# ADAS_ECU_revA.net
KiCad netlist of a schematic drawn in Altium Designer
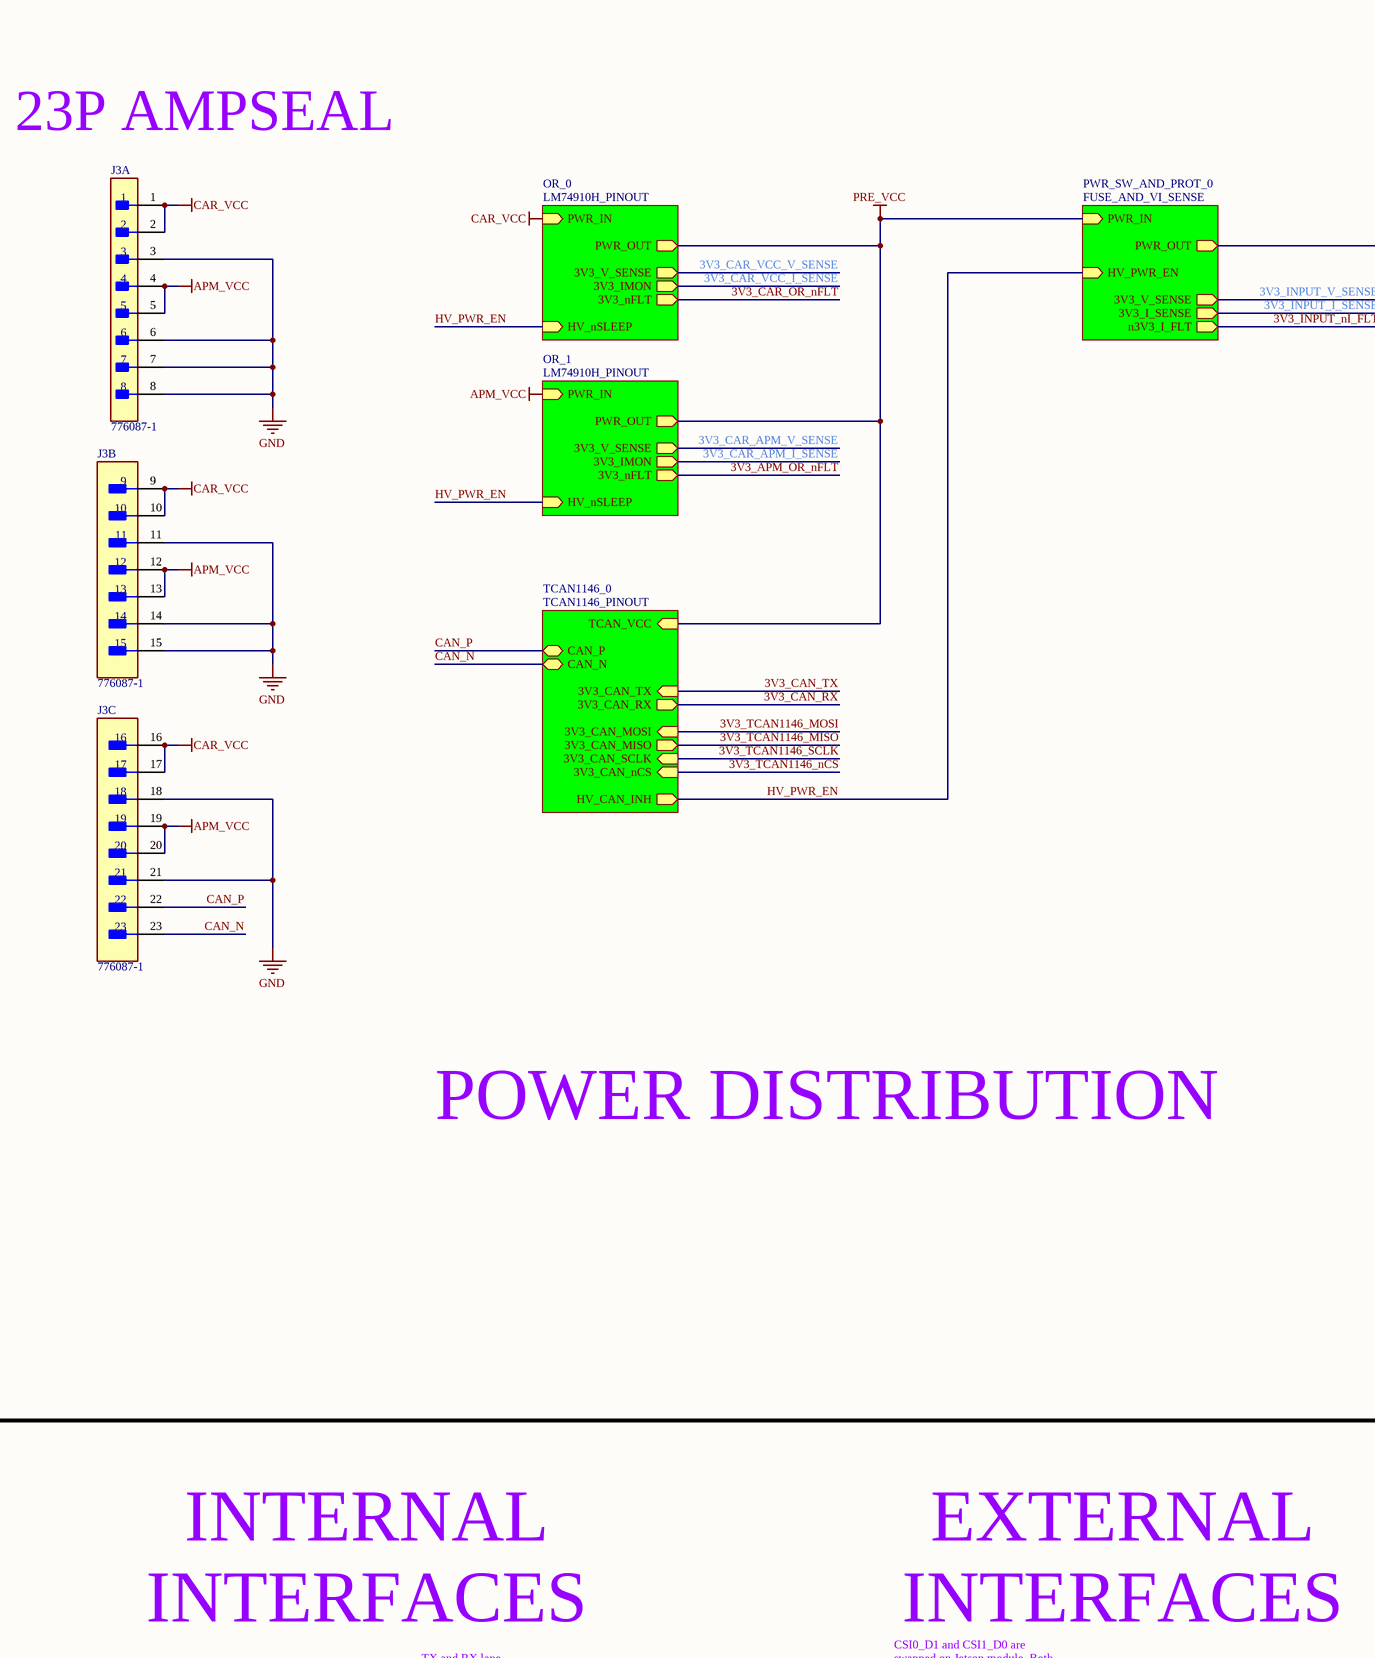
[diagram p0: ADAS_ECU_revA.SchDoc, top column 1 of 4]
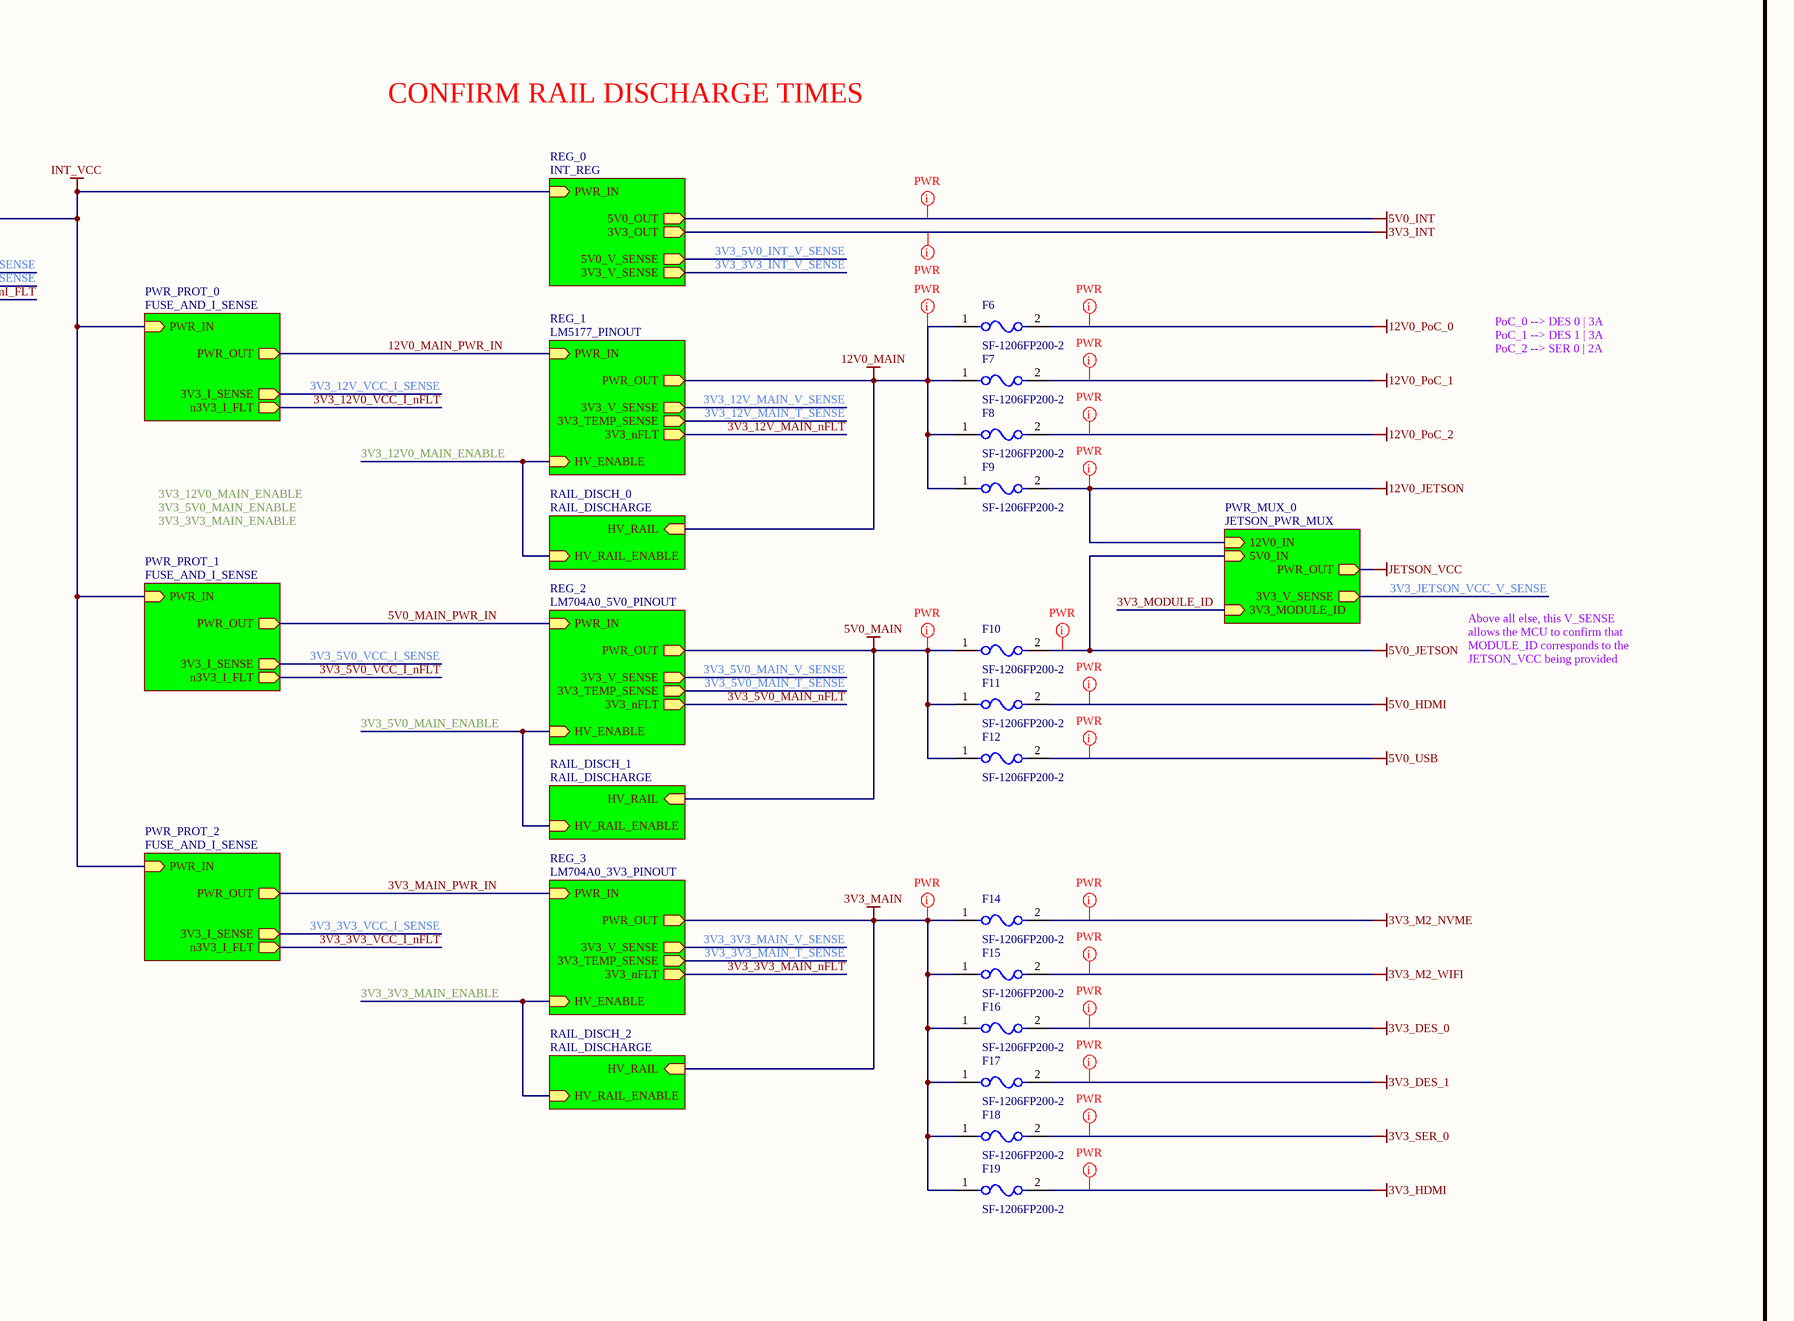
[diagram p1: ADAS_ECU_revA.SchDoc, top column 2 of 4]
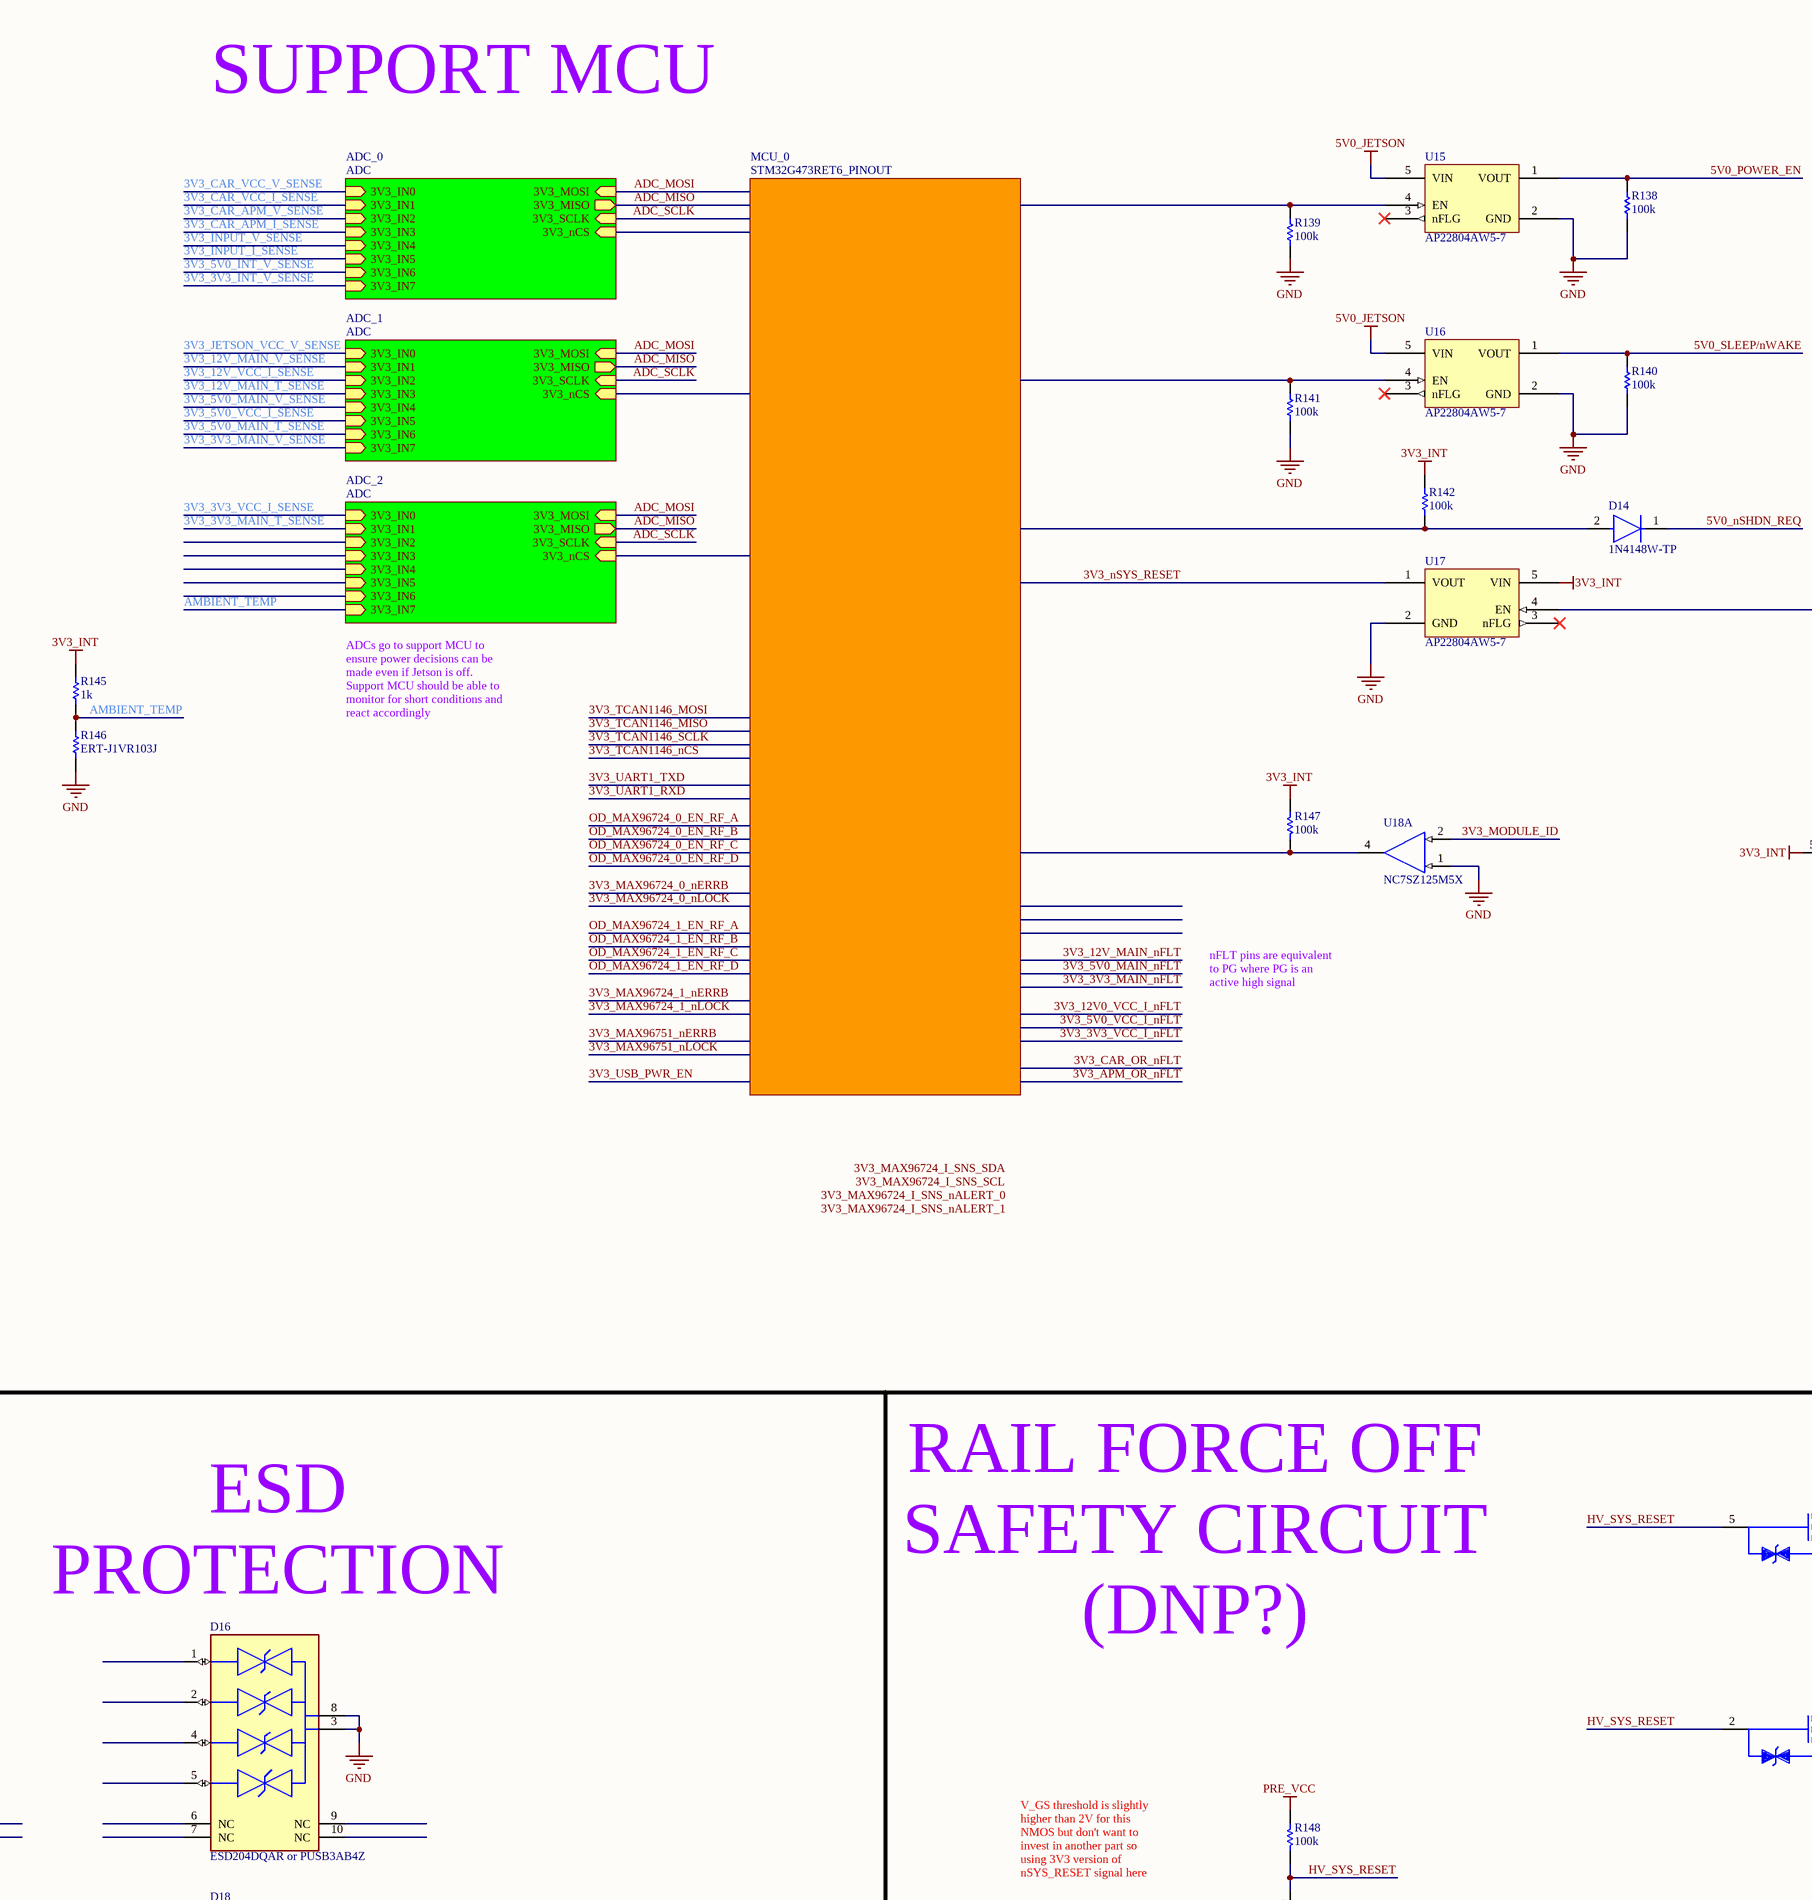
[diagram p2: ADAS_ECU_revA.SchDoc, top column 3 of 4]
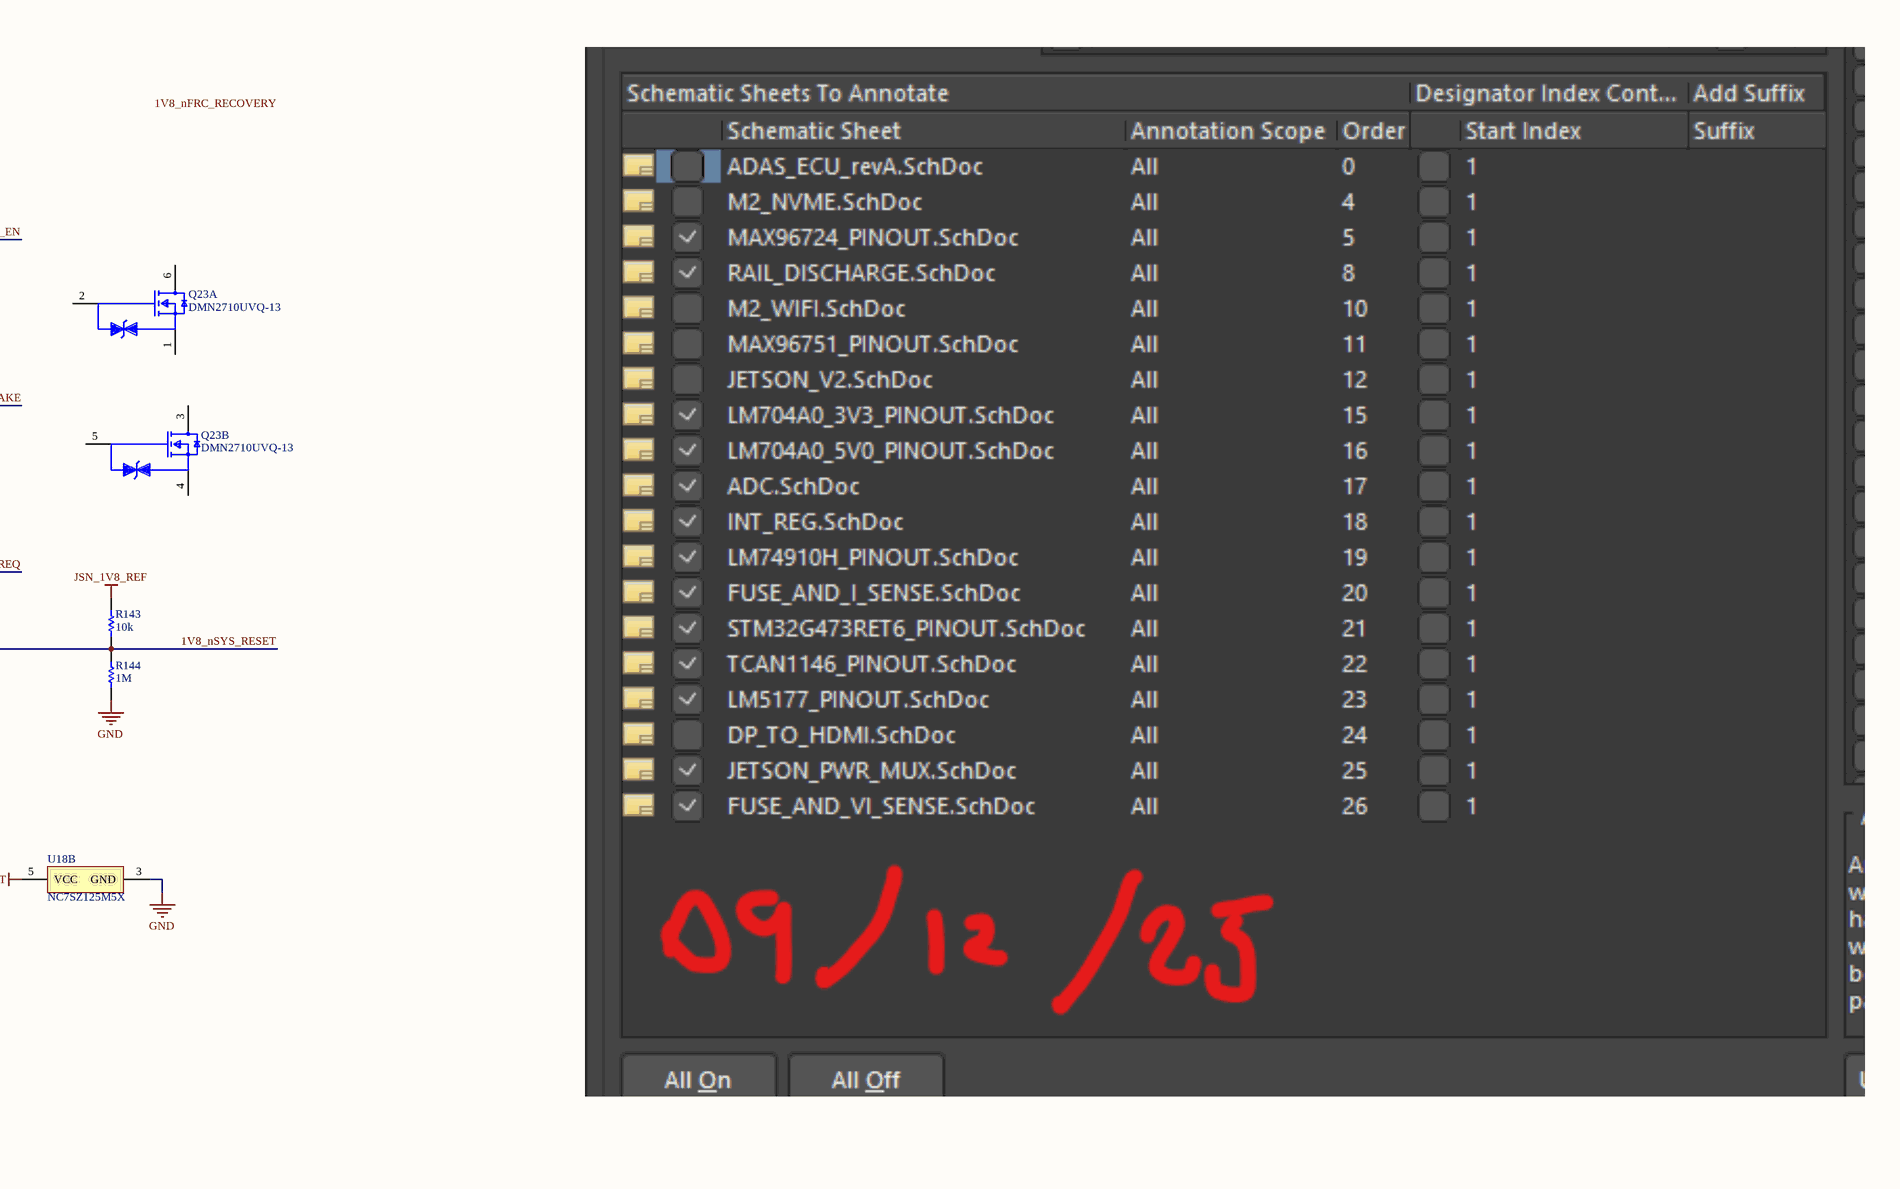
[diagram p3: ADAS_ECU_revA.SchDoc, top column 4 of 4]
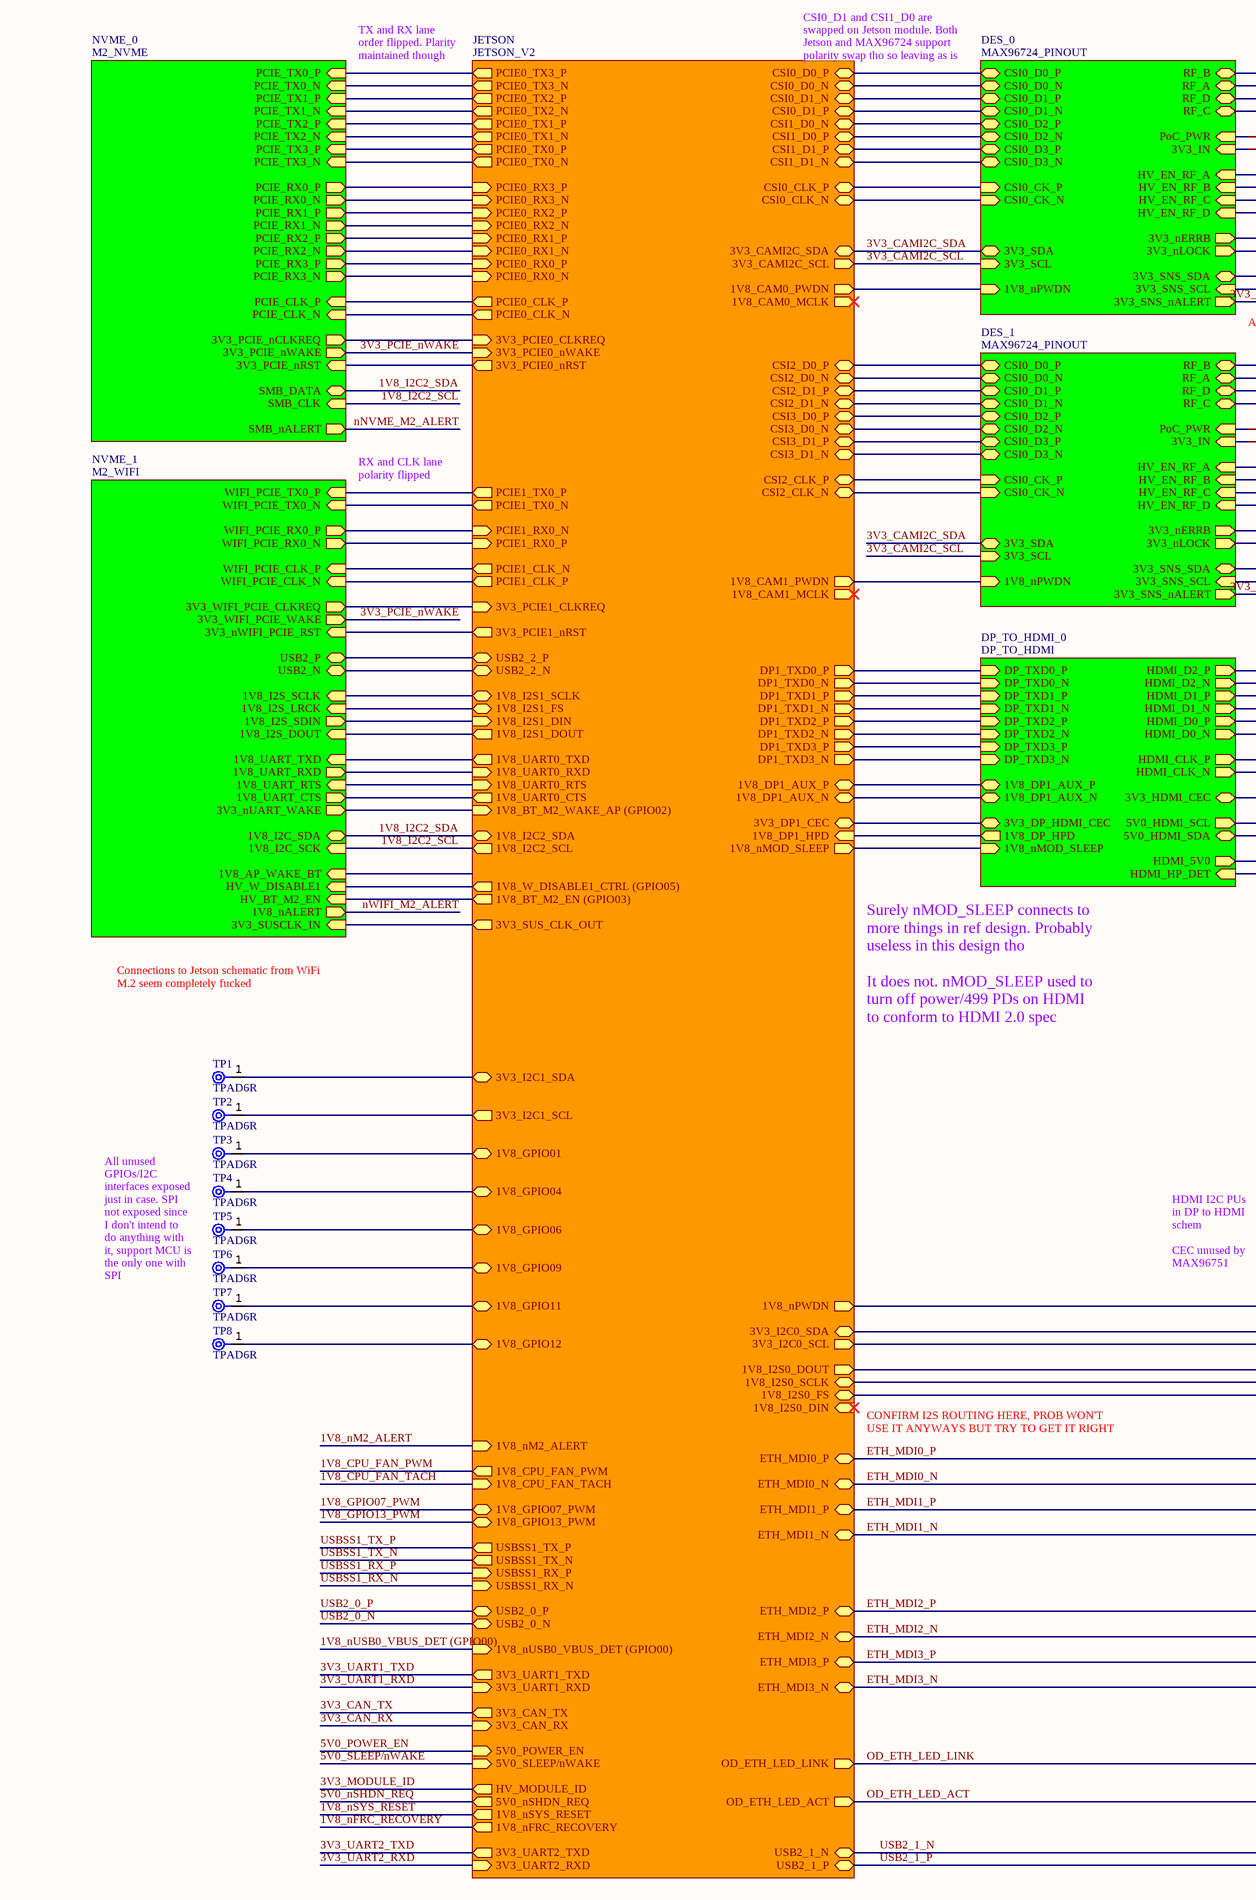
[diagram p4: ADAS_ECU_revA.SchDoc, centre column 1 of 4]
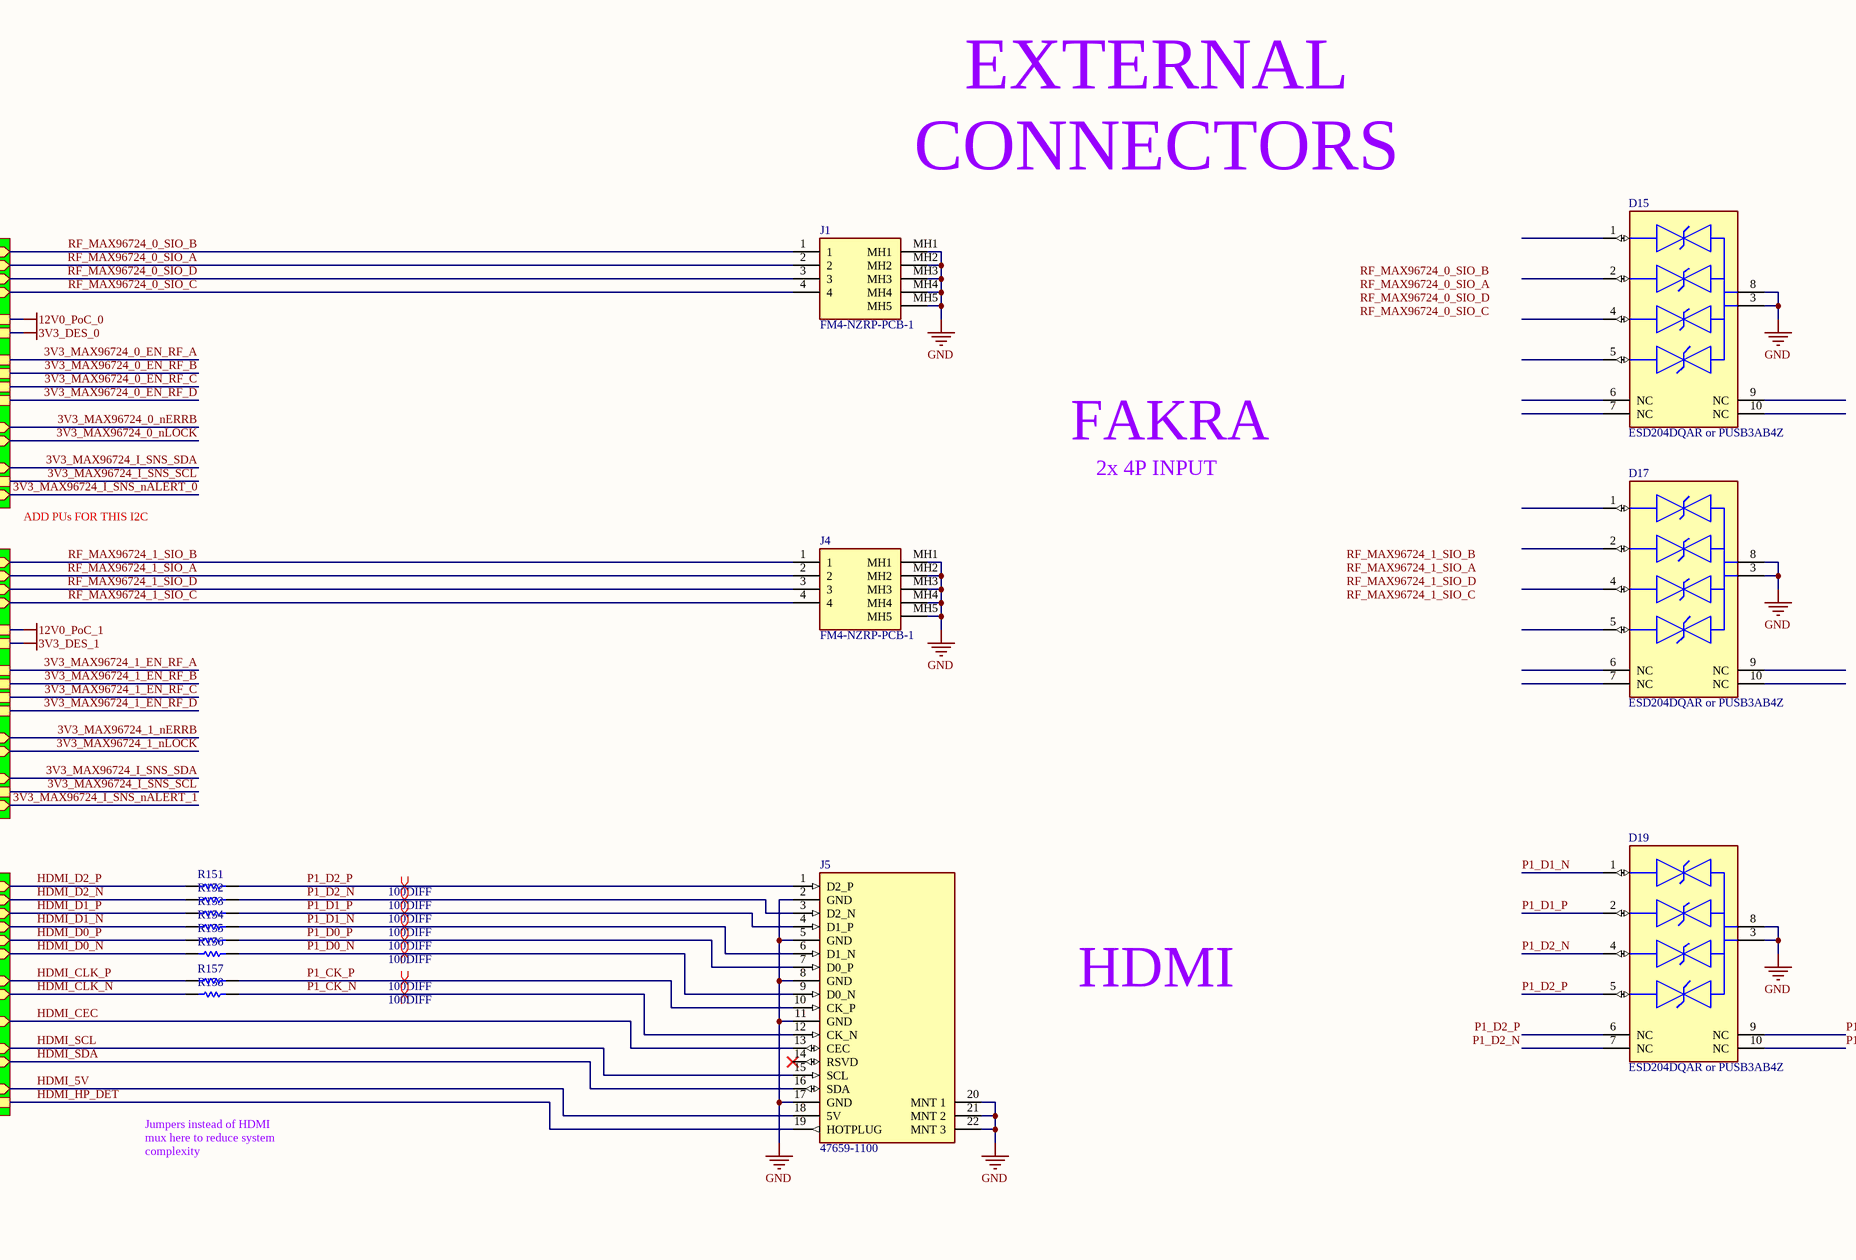
[diagram p5: ADAS_ECU_revA.SchDoc, centre column 2 of 4]
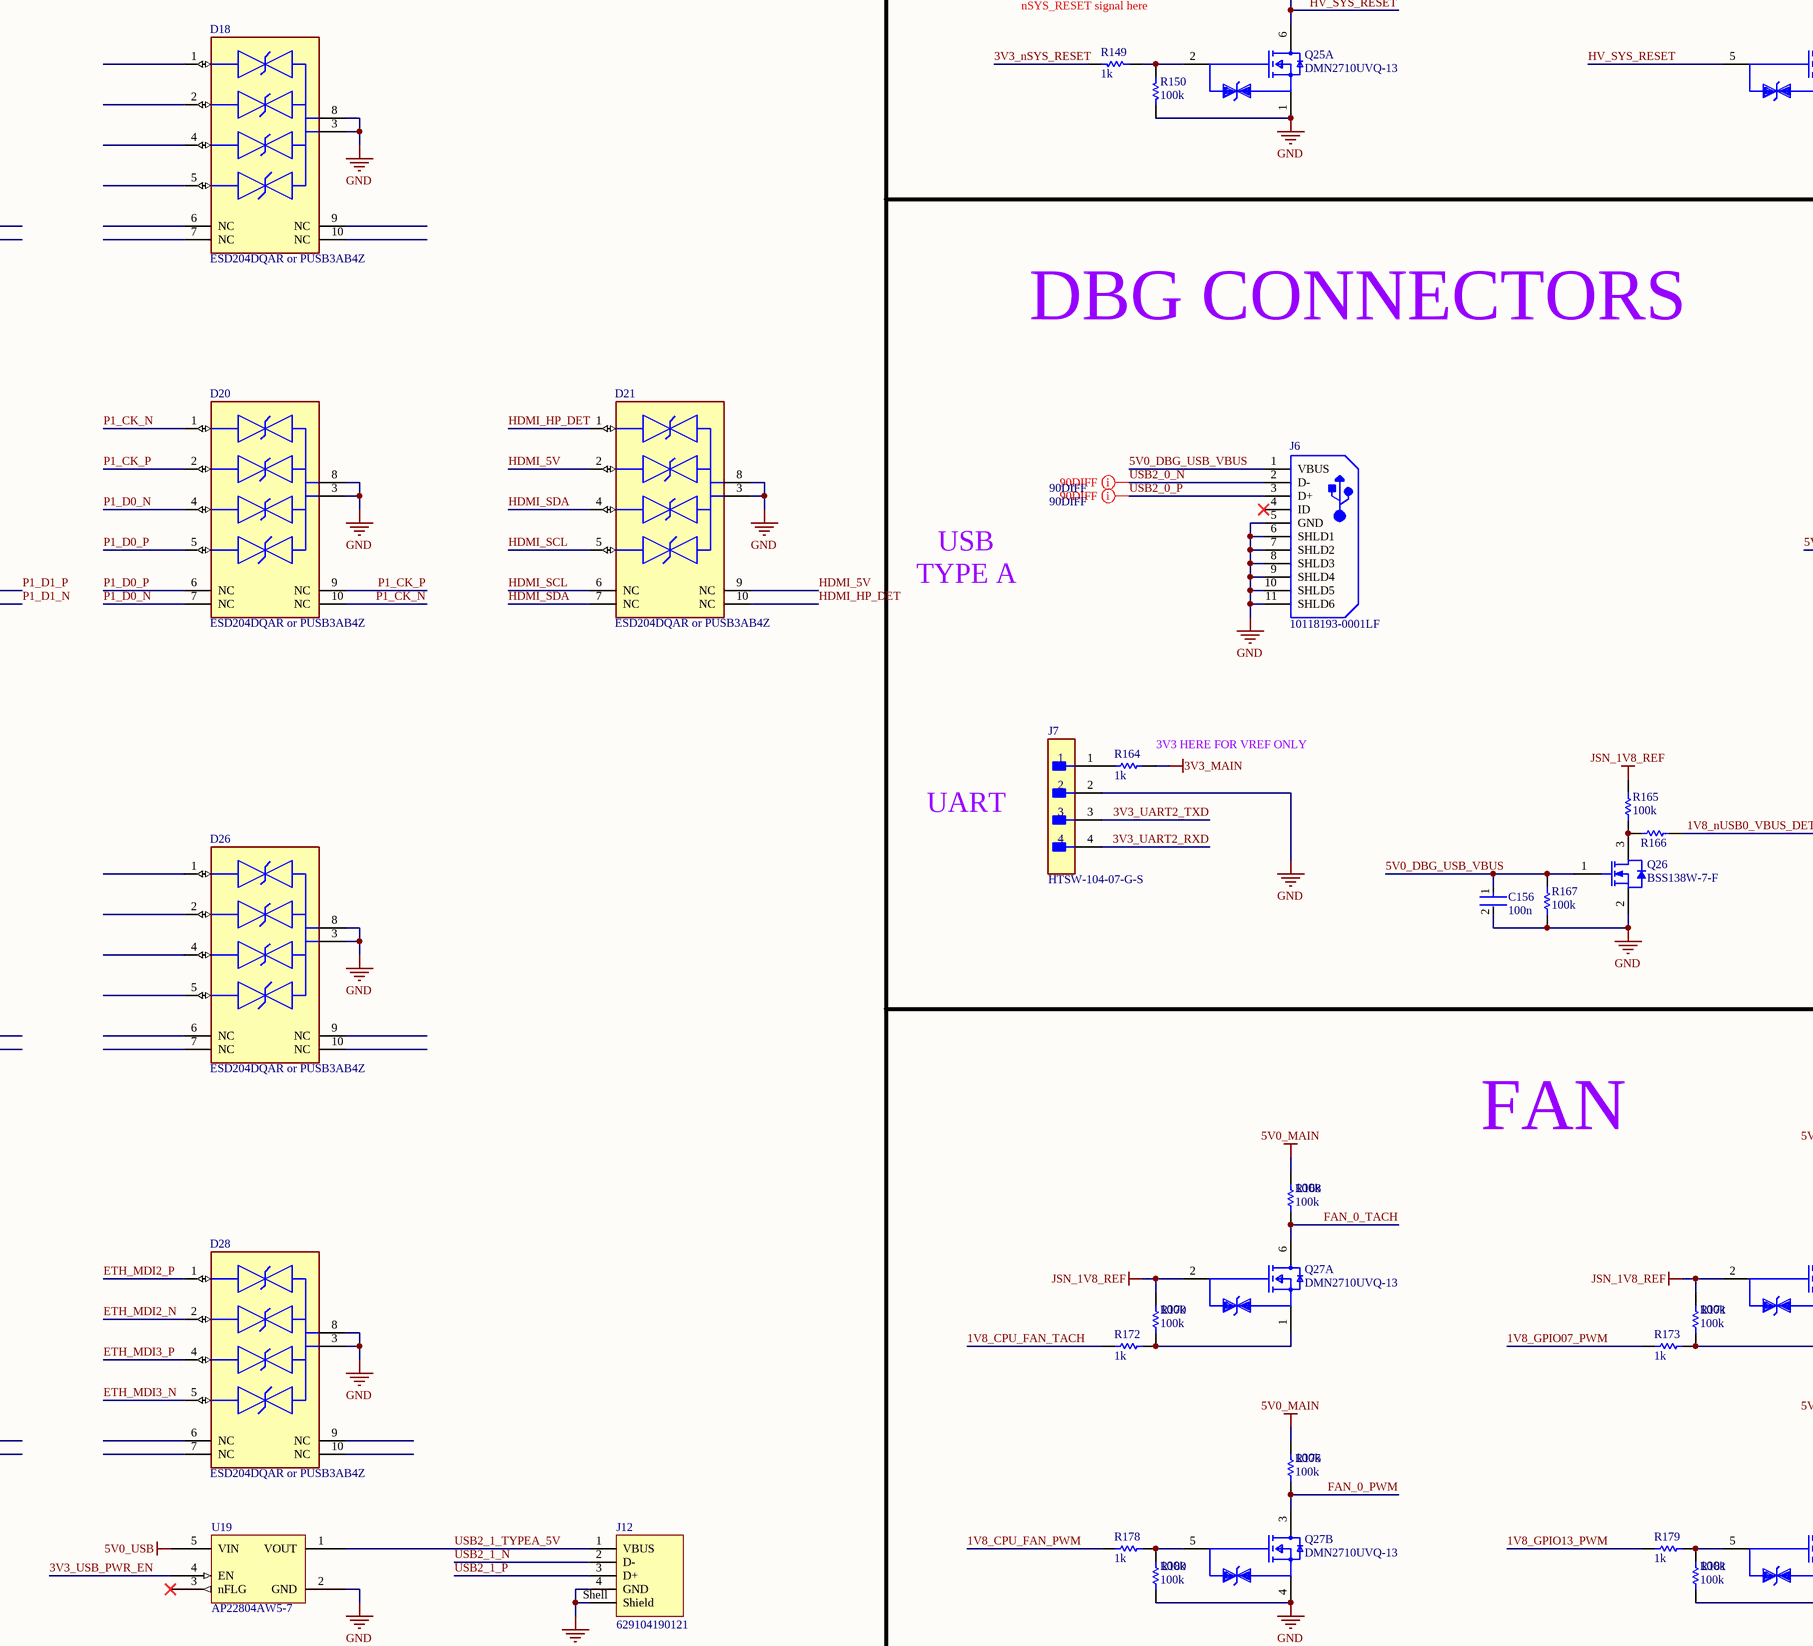
[diagram p6: ADAS_ECU_revA.SchDoc, centre column 3 of 4]
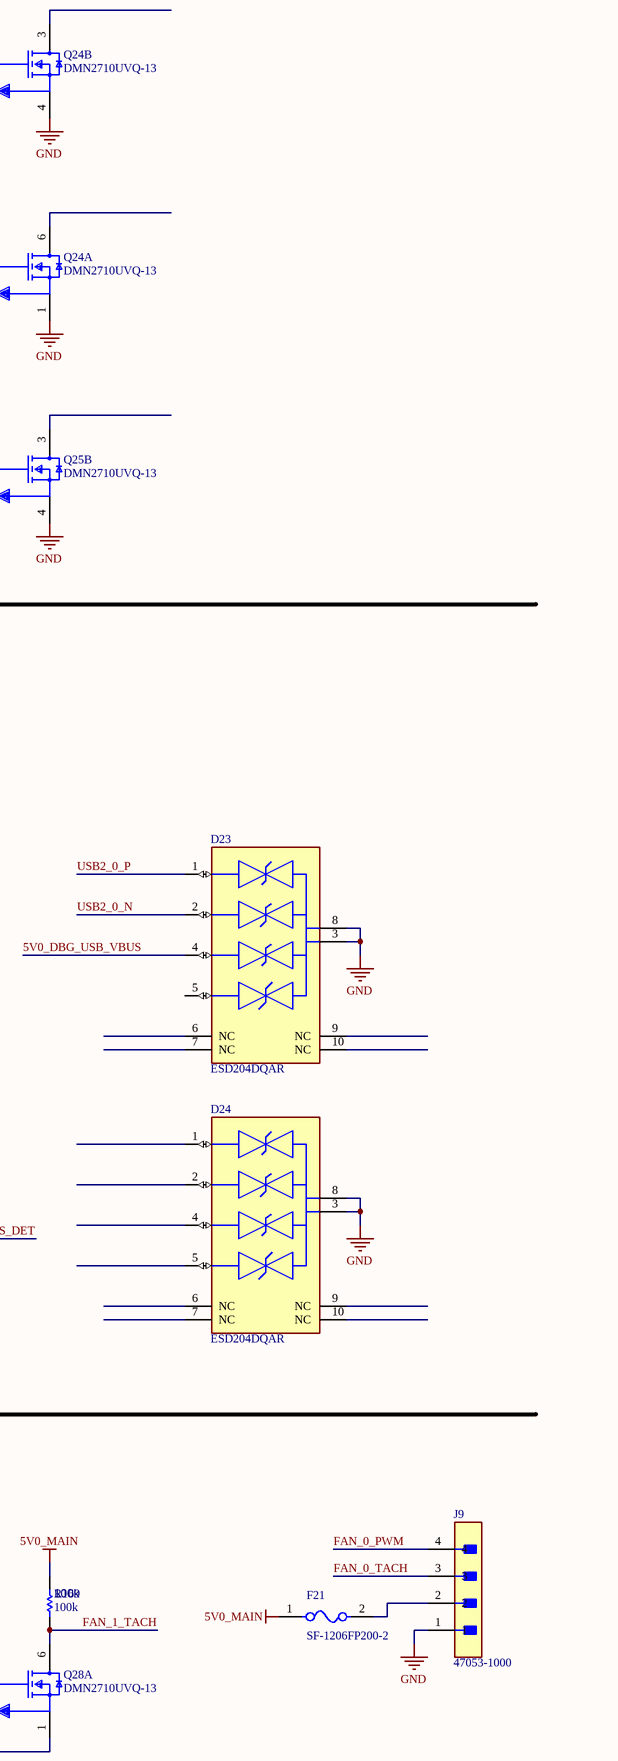
[diagram p7: ADAS_ECU_revA.SchDoc, centre column 4 of 4]
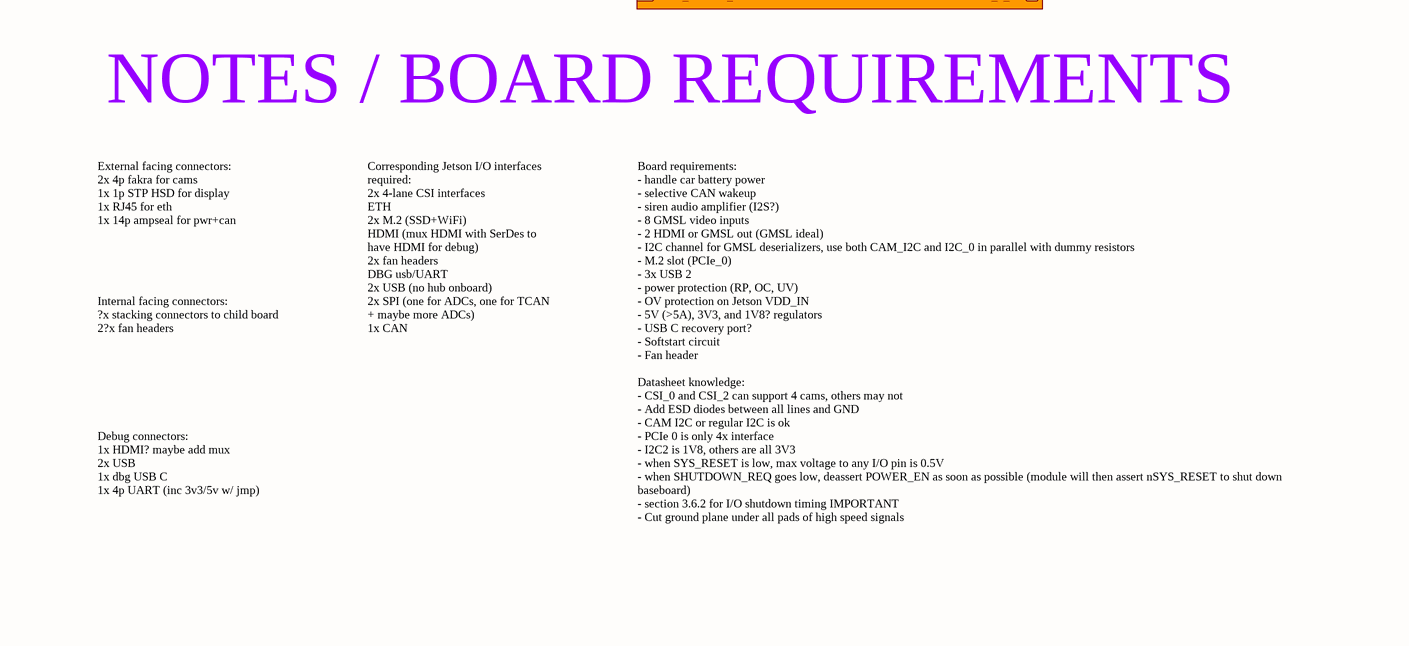
[diagram p8: ADAS_ECU_revA.SchDoc, bottom column 1 of 4]
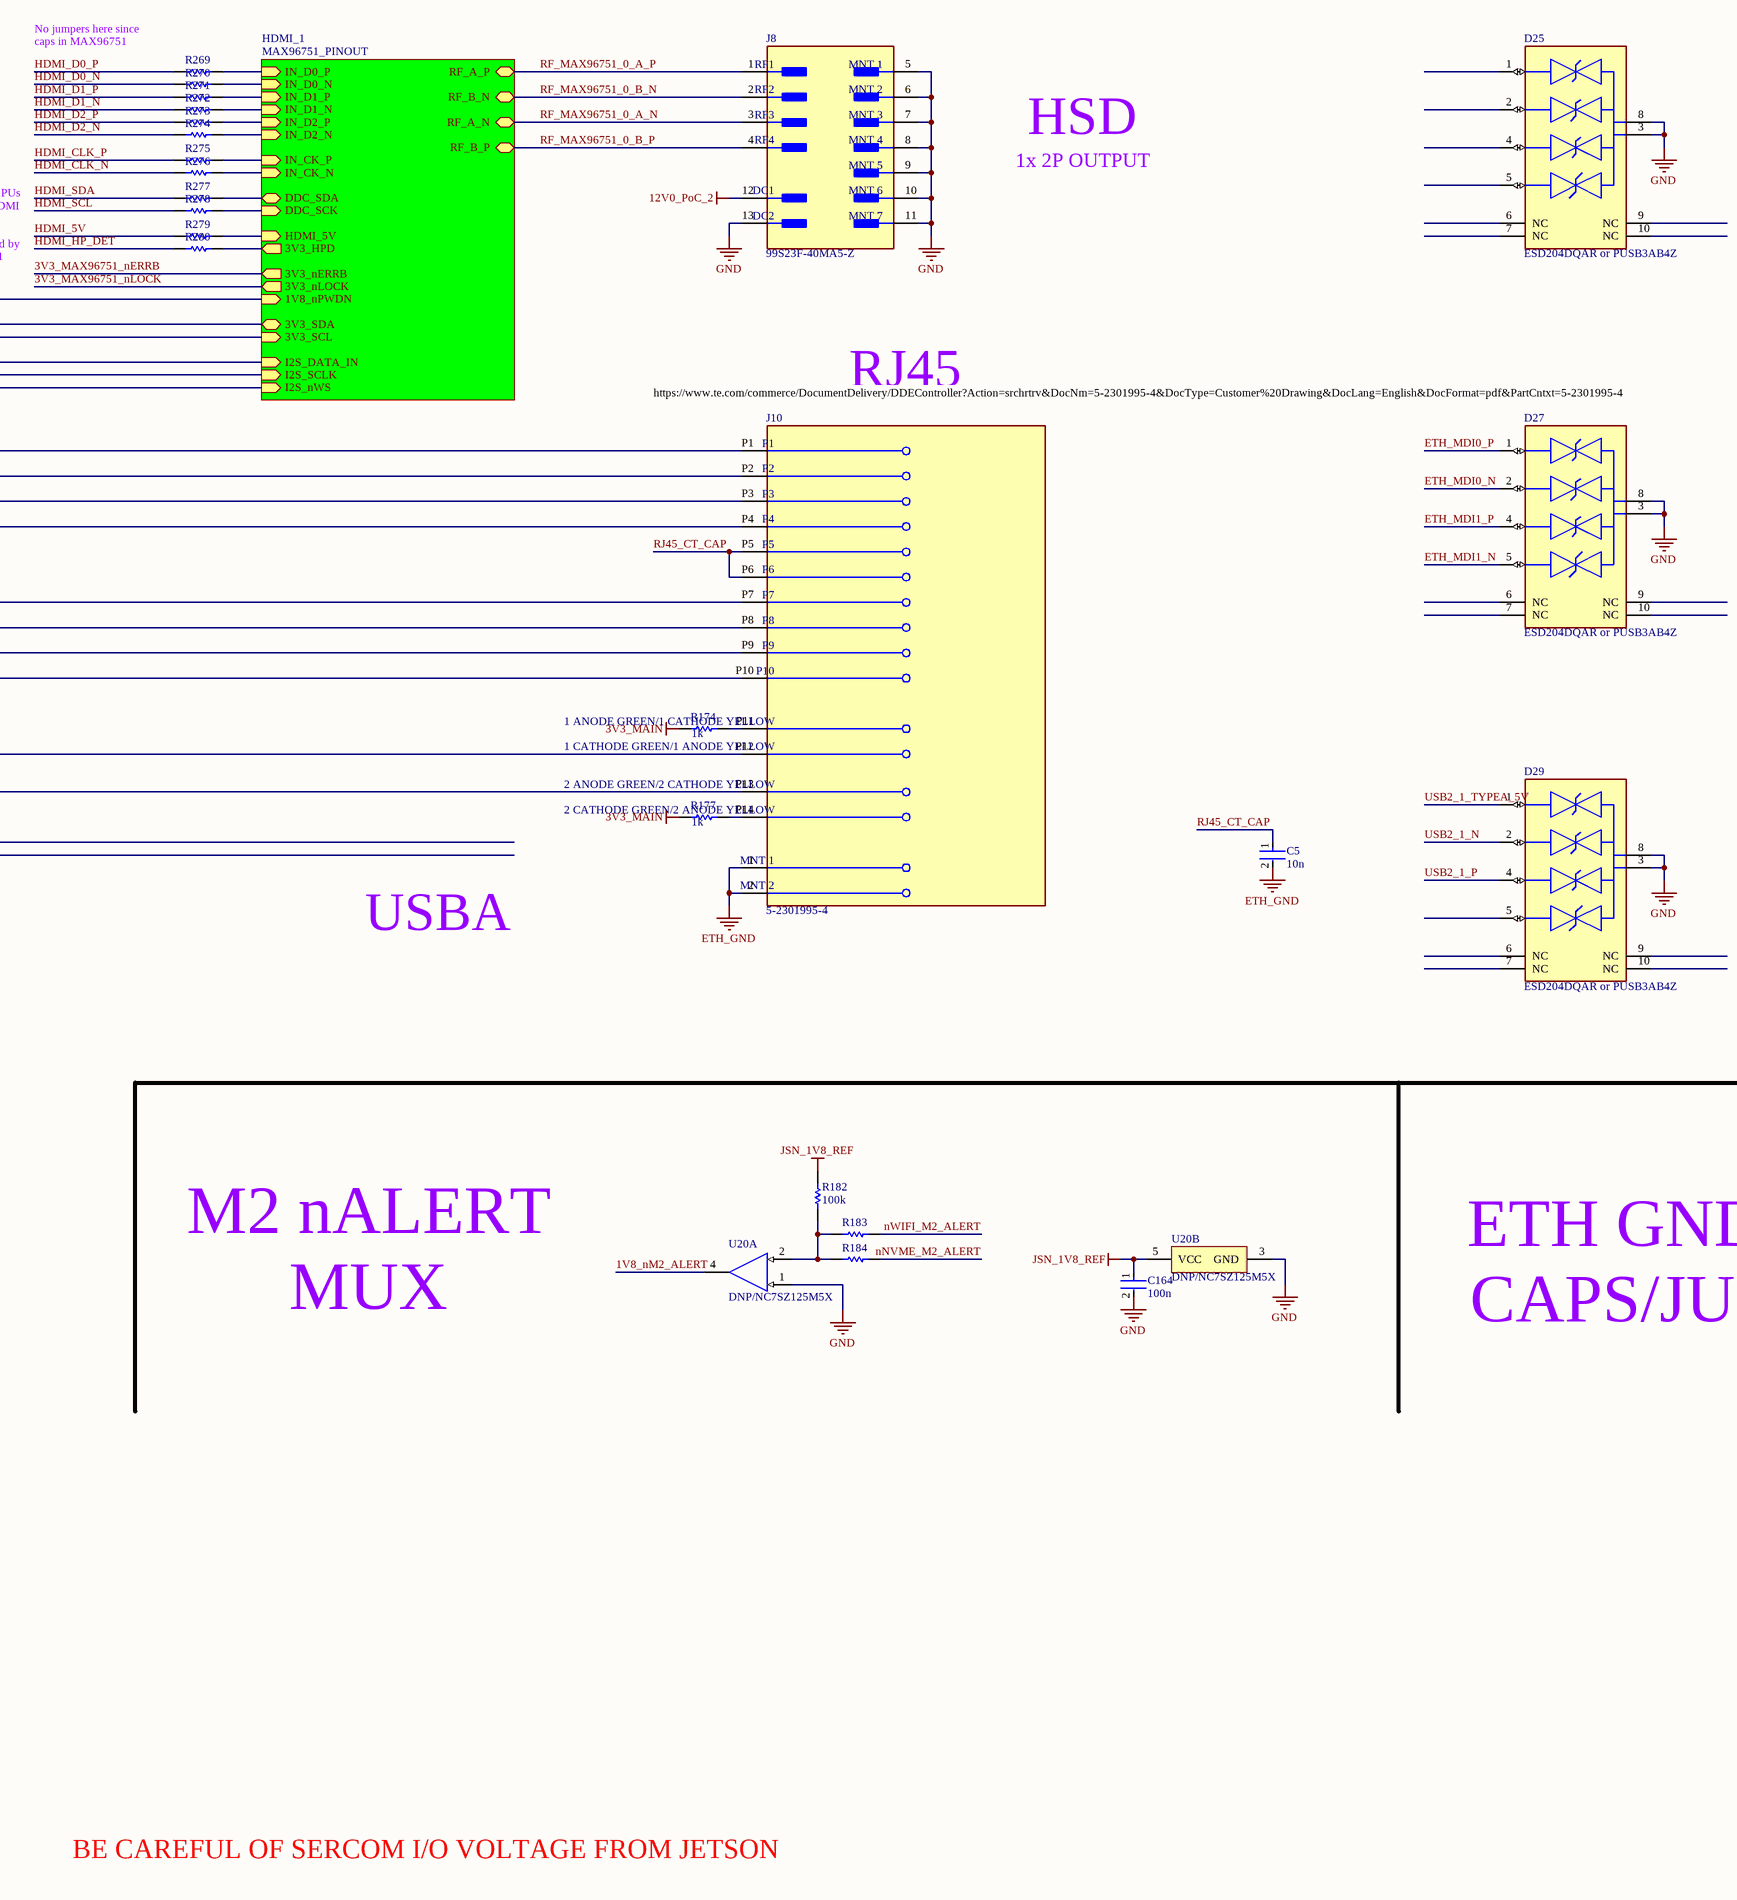
[diagram p9: ADAS_ECU_revA.SchDoc, bottom column 2 of 4]
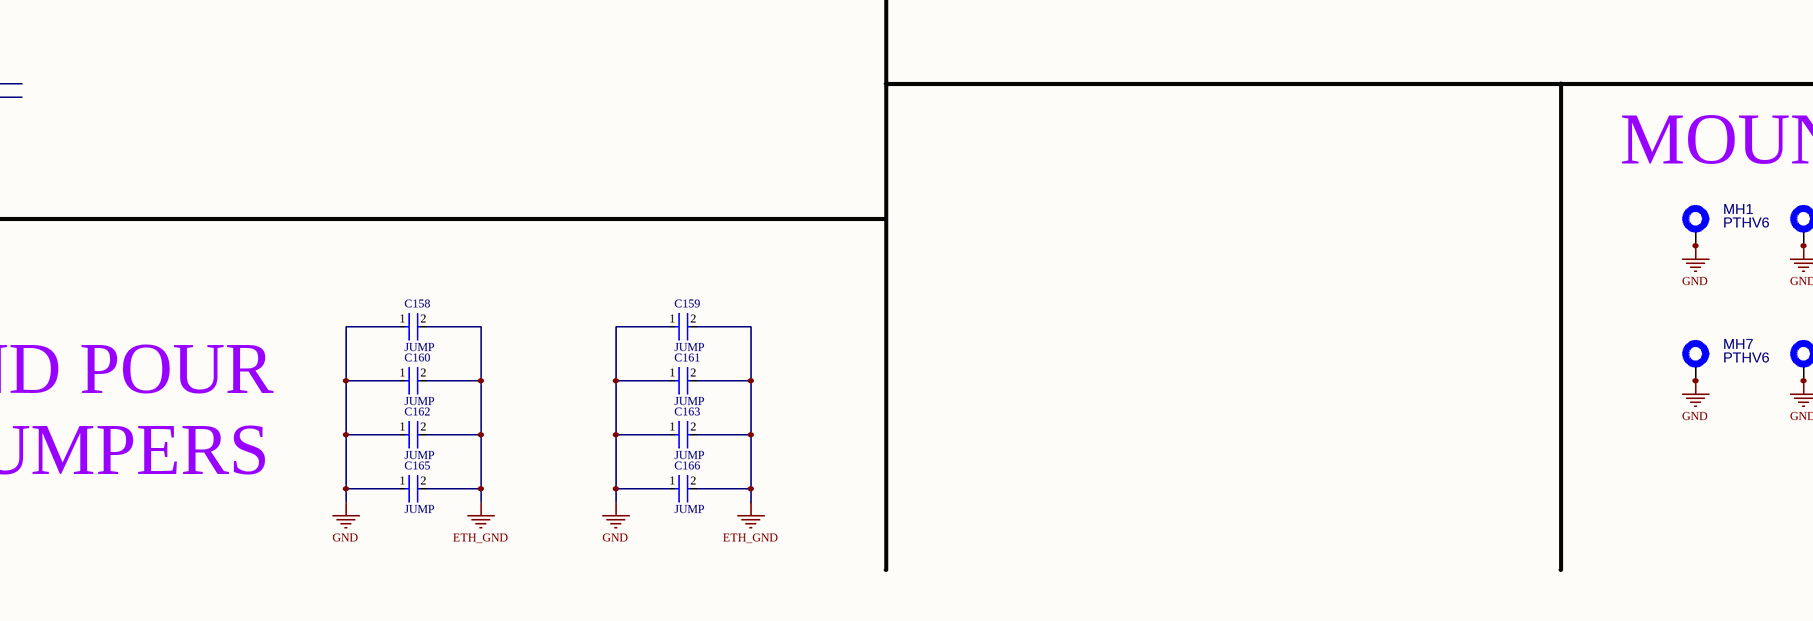
[diagram p10: ADAS_ECU_revA.SchDoc, bottom column 3 of 4]
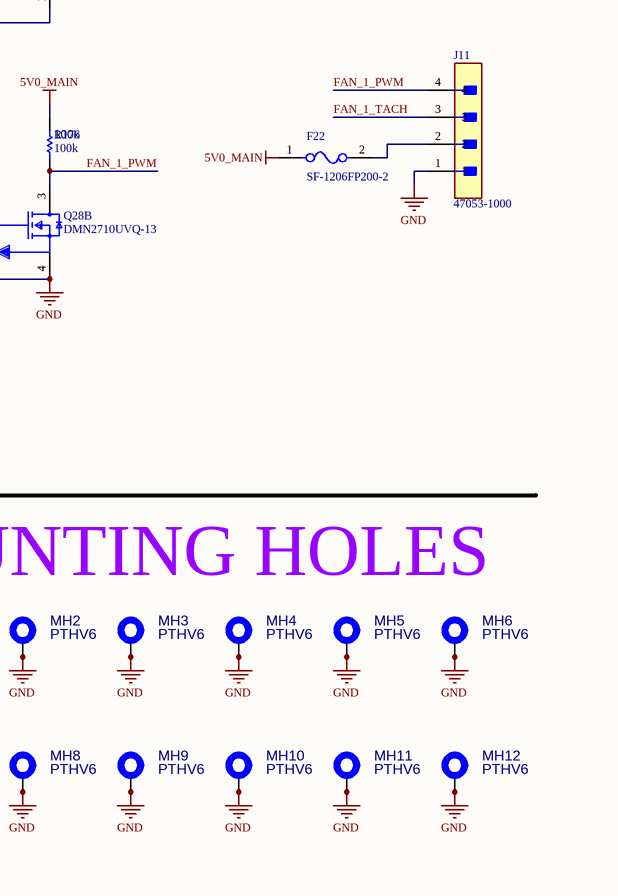
[diagram p11: ADAS_ECU_revA.SchDoc, bottom column 4 of 4]

(export (version "E")
  (design (tool "Eeschema 10.0.6"))
  (components
    (comp (ref "C5")
      (value "10n")
      (footprint "FP-0402-L_1_0_0_05-W_0_5-IPC_A")
      (description "LARGE PADS, 0402 CAP, CHANGE COMMENT TO MATCH REAL P/N")
      (libsource (lib "Space Concordia") (part "b4654b650e69147ec39a6b967a45e02"))
    )
    (comp (ref "C156")
      (value "100n")
      (footprint "FP-0402-L_1_0_0_05-W_0_5-IPC_A")
      (description "LARGE PADS, 0402 CAP, CHANGE COMMENT TO MATCH REAL P/N")
      (libsource (lib "Space Concordia") (part "b4654b650e69147ec39a6b967a45e02"))
    )
    (comp (ref "C158")
      (value "JUMP")
      (footprint "FP-0402-L_1_0_0_05-W_0_5-IPC_A")
      (description "LARGE PADS, 0402 CAP, CHANGE COMMENT TO MATCH REAL P/N")
      (libsource (lib "Space Concordia") (part "b4654b650e69147ec39a6b967a45e02"))
    )
    (comp (ref "C159")
      (value "JUMP")
      (footprint "FP-0402-L_1_0_0_05-W_0_5-IPC_A")
      (description "LARGE PADS, 0402 CAP, CHANGE COMMENT TO MATCH REAL P/N")
      (libsource (lib "Space Concordia") (part "b4654b650e69147ec39a6b967a45e02"))
    )
    (comp (ref "C160")
      (value "JUMP")
      (footprint "FP-0402-L_1_0_0_05-W_0_5-IPC_A")
      (description "LARGE PADS, 0402 CAP, CHANGE COMMENT TO MATCH REAL P/N")
      (libsource (lib "Space Concordia") (part "b4654b650e69147ec39a6b967a45e02"))
    )
    (comp (ref "C161")
      (value "JUMP")
      (footprint "FP-0402-L_1_0_0_05-W_0_5-IPC_A")
      (description "LARGE PADS, 0402 CAP, CHANGE COMMENT TO MATCH REAL P/N")
      (libsource (lib "Space Concordia") (part "b4654b650e69147ec39a6b967a45e02"))
    )
    (comp (ref "C162")
      (value "JUMP")
      (footprint "FP-0402-L_1_0_0_05-W_0_5-IPC_A")
      (description "LARGE PADS, 0402 CAP, CHANGE COMMENT TO MATCH REAL P/N")
      (libsource (lib "Space Concordia") (part "b4654b650e69147ec39a6b967a45e02"))
    )
    (comp (ref "C163")
      (value "JUMP")
      (footprint "FP-0402-L_1_0_0_05-W_0_5-IPC_A")
      (description "LARGE PADS, 0402 CAP, CHANGE COMMENT TO MATCH REAL P/N")
      (libsource (lib "Space Concordia") (part "b4654b650e69147ec39a6b967a45e02"))
    )
    (comp (ref "C164")
      (value "100n")
      (footprint "FP-0402-L_1_0_0_05-W_0_5-IPC_A")
      (description "LARGE PADS, 0402 CAP, CHANGE COMMENT TO MATCH REAL P/N")
      (libsource (lib "Space Concordia") (part "b4654b650e69147ec39a6b967a45e02"))
    )
    (comp (ref "C165")
      (value "JUMP")
      (footprint "FP-0402-L_1_0_0_05-W_0_5-IPC_A")
      (description "LARGE PADS, 0402 CAP, CHANGE COMMENT TO MATCH REAL P/N")
      (libsource (lib "Space Concordia") (part "b4654b650e69147ec39a6b967a45e02"))
    )
    (comp (ref "C166")
      (value "JUMP")
      (footprint "FP-0402-L_1_0_0_05-W_0_5-IPC_A")
      (description "LARGE PADS, 0402 CAP, CHANGE COMMENT TO MATCH REAL P/N")
      (libsource (lib "Space Concordia") (part "b4654b650e69147ec39a6b967a45e02"))
    )
    (comp (ref "D14")
      (value "1N4148W-TP")
      (footprint "FP-SOD-123-IPC_A")
      (description "DIODE GEN PURP 100V 150MA SOD123")
      (libsource (lib "Altium Content Vault") (part "d7152d700b627762746794eb795d46e"))
    )
    (comp (ref "D15")
      (value "ESD204DQAR or PUSB3AB4Z")
      (footprint "FP-DQA0010A-MFG")
      (description "4-CHANNEL LOW-CAPACITANCE SURGE")
      (fields
        (field (name "MANUFACTURER") "Texas Instruments")
        (field (name "OCTOPART") "https://octopart.com/esd204dqar-texas+instruments-89917476")
      )
      (libsource (lib "Altium Content Vault") (part "1465e58c1818c7767b55926832f0bf5"))
    )
    (comp (ref "D16")
      (value "ESD204DQAR or PUSB3AB4Z")
      (footprint "FP-DQA0010A-MFG")
      (description "4-CHANNEL LOW-CAPACITANCE SURGE")
      (fields
        (field (name "MANUFACTURER") "Texas Instruments")
        (field (name "OCTOPART") "https://octopart.com/esd204dqar-texas+instruments-89917476")
      )
      (libsource (lib "Altium Content Vault") (part "1465e58c1818c7767b55926832f0bf5"))
    )
    (comp (ref "D17")
      (value "ESD204DQAR or PUSB3AB4Z")
      (footprint "FP-DQA0010A-MFG")
      (description "4-CHANNEL LOW-CAPACITANCE SURGE")
      (fields
        (field (name "MANUFACTURER") "Texas Instruments")
        (field (name "OCTOPART") "https://octopart.com/esd204dqar-texas+instruments-89917476")
      )
      (libsource (lib "Altium Content Vault") (part "1465e58c1818c7767b55926832f0bf5"))
    )
    (comp (ref "D18")
      (value "ESD204DQAR or PUSB3AB4Z")
      (footprint "FP-DQA0010A-MFG")
      (description "4-CHANNEL LOW-CAPACITANCE SURGE")
      (fields
        (field (name "MANUFACTURER") "Texas Instruments")
        (field (name "OCTOPART") "https://octopart.com/esd204dqar-texas+instruments-89917476")
      )
      (libsource (lib "Altium Content Vault") (part "1465e58c1818c7767b55926832f0bf5"))
    )
    (comp (ref "D19")
      (value "ESD204DQAR or PUSB3AB4Z")
      (footprint "FP-DQA0010A-MFG")
      (description "4-CHANNEL LOW-CAPACITANCE SURGE")
      (fields
        (field (name "MANUFACTURER") "Texas Instruments")
        (field (name "OCTOPART") "https://octopart.com/esd204dqar-texas+instruments-89917476")
      )
      (libsource (lib "Altium Content Vault") (part "1465e58c1818c7767b55926832f0bf5"))
    )
    (comp (ref "D20")
      (value "ESD204DQAR or PUSB3AB4Z")
      (footprint "FP-DQA0010A-MFG")
      (description "4-CHANNEL LOW-CAPACITANCE SURGE")
      (fields
        (field (name "MANUFACTURER") "Texas Instruments")
        (field (name "OCTOPART") "https://octopart.com/esd204dqar-texas+instruments-89917476")
      )
      (libsource (lib "Altium Content Vault") (part "1465e58c1818c7767b55926832f0bf5"))
    )
    (comp (ref "D21")
      (value "ESD204DQAR or PUSB3AB4Z")
      (footprint "FP-DQA0010A-MFG")
      (description "4-CHANNEL LOW-CAPACITANCE SURGE")
      (fields
        (field (name "MANUFACTURER") "Texas Instruments")
        (field (name "OCTOPART") "https://octopart.com/esd204dqar-texas+instruments-89917476")
      )
      (libsource (lib "Altium Content Vault") (part "1465e58c1818c7767b55926832f0bf5"))
    )
    (comp (ref "D23")
      (value "ESD204DQAR")
      (footprint "FP-DQA0010A-MFG")
      (description "4-CHANNEL LOW-CAPACITANCE SURGE")
      (fields
        (field (name "MANUFACTURER") "Texas Instruments")
        (field (name "OCTOPART") "https://octopart.com/esd204dqar-texas+instruments-89917476")
      )
      (libsource (lib "Altium Content Vault") (part "1465e58c1818c7767b55926832f0bf5"))
    )
    (comp (ref "D24")
      (value "ESD204DQAR")
      (footprint "FP-DQA0010A-MFG")
      (description "4-CHANNEL LOW-CAPACITANCE SURGE")
      (fields
        (field (name "MANUFACTURER") "Texas Instruments")
        (field (name "OCTOPART") "https://octopart.com/esd204dqar-texas+instruments-89917476")
      )
      (libsource (lib "Altium Content Vault") (part "1465e58c1818c7767b55926832f0bf5"))
    )
    (comp (ref "D25")
      (value "ESD204DQAR or PUSB3AB4Z")
      (footprint "FP-DQA0010A-MFG")
      (description "4-CHANNEL LOW-CAPACITANCE SURGE")
      (fields
        (field (name "MANUFACTURER") "Texas Instruments")
        (field (name "OCTOPART") "https://octopart.com/esd204dqar-texas+instruments-89917476")
      )
      (libsource (lib "Altium Content Vault") (part "1465e58c1818c7767b55926832f0bf5"))
    )
    (comp (ref "D26")
      (value "ESD204DQAR or PUSB3AB4Z")
      (footprint "FP-DQA0010A-MFG")
      (description "4-CHANNEL LOW-CAPACITANCE SURGE")
      (fields
        (field (name "MANUFACTURER") "Texas Instruments")
        (field (name "OCTOPART") "https://octopart.com/esd204dqar-texas+instruments-89917476")
      )
      (libsource (lib "Altium Content Vault") (part "1465e58c1818c7767b55926832f0bf5"))
    )
    (comp (ref "D27")
      (value "ESD204DQAR or PUSB3AB4Z")
      (footprint "FP-DQA0010A-MFG")
      (description "4-CHANNEL LOW-CAPACITANCE SURGE")
      (fields
        (field (name "MANUFACTURER") "Texas Instruments")
        (field (name "OCTOPART") "https://octopart.com/esd204dqar-texas+instruments-89917476")
      )
      (libsource (lib "Altium Content Vault") (part "1465e58c1818c7767b55926832f0bf5"))
    )
    (comp (ref "D28")
      (value "ESD204DQAR or PUSB3AB4Z")
      (footprint "FP-DQA0010A-MFG")
      (description "4-CHANNEL LOW-CAPACITANCE SURGE")
      (fields
        (field (name "MANUFACTURER") "Texas Instruments")
        (field (name "OCTOPART") "https://octopart.com/esd204dqar-texas+instruments-89917476")
      )
      (libsource (lib "Altium Content Vault") (part "1465e58c1818c7767b55926832f0bf5"))
    )
    (comp (ref "D29")
      (value "ESD204DQAR or PUSB3AB4Z")
      (footprint "FP-DQA0010A-MFG")
      (description "4-CHANNEL LOW-CAPACITANCE SURGE")
      (fields
        (field (name "MANUFACTURER") "Texas Instruments")
        (field (name "OCTOPART") "https://octopart.com/esd204dqar-texas+instruments-89917476")
      )
      (libsource (lib "Altium Content Vault") (part "1465e58c1818c7767b55926832f0bf5"))
    )
    (comp (ref "F6")
      (value "SF-1206FP200-2")
      (footprint "FP-SF-1206FP-MFG")
      (description "FUSE BOARD MOUNT 2A 63VDC 1206")
      (libsource (lib "Altium Content Vault") (part "5bcf9b9f640e542cf0359d10258e979"))
    )
    (comp (ref "F7")
      (value "SF-1206FP200-2")
      (footprint "FP-SF-1206FP-MFG")
      (description "FUSE BOARD MOUNT 2A 63VDC 1206")
      (libsource (lib "Altium Content Vault") (part "5bcf9b9f640e542cf0359d10258e979"))
    )
    (comp (ref "F8")
      (value "SF-1206FP200-2")
      (footprint "FP-SF-1206FP-MFG")
      (description "FUSE BOARD MOUNT 2A 63VDC 1206")
      (libsource (lib "Altium Content Vault") (part "5bcf9b9f640e542cf0359d10258e979"))
    )
    (comp (ref "F9")
      (value "SF-1206FP200-2")
      (footprint "FP-SF-1206FP-MFG")
      (description "FUSE BOARD MOUNT 2A 63VDC 1206")
      (libsource (lib "Altium Content Vault") (part "5bcf9b9f640e542cf0359d10258e979"))
    )
    (comp (ref "F10")
      (value "SF-1206FP200-2")
      (footprint "FP-SF-1206FP-MFG")
      (description "FUSE BOARD MOUNT 2A 63VDC 1206")
      (libsource (lib "Altium Content Vault") (part "5bcf9b9f640e542cf0359d10258e979"))
    )
    (comp (ref "F11")
      (value "SF-1206FP200-2")
      (footprint "FP-SF-1206FP-MFG")
      (description "FUSE BOARD MOUNT 2A 63VDC 1206")
      (libsource (lib "Altium Content Vault") (part "5bcf9b9f640e542cf0359d10258e979"))
    )
    (comp (ref "F12")
      (value "SF-1206FP200-2")
      (footprint "FP-SF-1206FP-MFG")
      (description "FUSE BOARD MOUNT 2A 63VDC 1206")
      (libsource (lib "Altium Content Vault") (part "5bcf9b9f640e542cf0359d10258e979"))
    )
    (comp (ref "F14")
      (value "SF-1206FP200-2")
      (footprint "FP-SF-1206FP-MFG")
      (description "FUSE BOARD MOUNT 2A 63VDC 1206")
      (libsource (lib "Altium Content Vault") (part "5bcf9b9f640e542cf0359d10258e979"))
    )
    (comp (ref "F15")
      (value "SF-1206FP200-2")
      (footprint "FP-SF-1206FP-MFG")
      (description "FUSE BOARD MOUNT 2A 63VDC 1206")
      (libsource (lib "Altium Content Vault") (part "5bcf9b9f640e542cf0359d10258e979"))
    )
    (comp (ref "F16")
      (value "SF-1206FP200-2")
      (footprint "FP-SF-1206FP-MFG")
      (description "FUSE BOARD MOUNT 2A 63VDC 1206")
      (libsource (lib "Altium Content Vault") (part "5bcf9b9f640e542cf0359d10258e979"))
    )
    (comp (ref "F17")
      (value "SF-1206FP200-2")
      (footprint "FP-SF-1206FP-MFG")
      (description "FUSE BOARD MOUNT 2A 63VDC 1206")
      (libsource (lib "Altium Content Vault") (part "5bcf9b9f640e542cf0359d10258e979"))
    )
    (comp (ref "F18")
      (value "SF-1206FP200-2")
      (footprint "FP-SF-1206FP-MFG")
      (description "FUSE BOARD MOUNT 2A 63VDC 1206")
      (libsource (lib "Altium Content Vault") (part "5bcf9b9f640e542cf0359d10258e979"))
    )
    (comp (ref "F19")
      (value "SF-1206FP200-2")
      (footprint "FP-SF-1206FP-MFG")
      (description "FUSE BOARD MOUNT 2A 63VDC 1206")
      (libsource (lib "Altium Content Vault") (part "5bcf9b9f640e542cf0359d10258e979"))
    )
    (comp (ref "F21")
      (value "SF-1206FP200-2")
      (footprint "FP-SF-1206FP-MFG")
      (description "FUSE BOARD MOUNT 2A 63VDC 1206")
      (libsource (lib "Altium Content Vault") (part "5bcf9b9f640e542cf0359d10258e979"))
    )
    (comp (ref "F22")
      (value "SF-1206FP200-2")
      (footprint "FP-SF-1206FP-MFG")
      (description "FUSE BOARD MOUNT 2A 63VDC 1206")
      (libsource (lib "Altium Content Vault") (part "5bcf9b9f640e542cf0359d10258e979"))
    )
    (comp (ref "J1")
      (value "FM4-NZRP-PCB-1")
      (footprint "FM4-NZRP-PCB-1-Footprint-1")
      (description "Connector RF Mini-FAKRA Plug 9GHz 50Ohm Solder Right Angle Through Hole")
      (libsource (lib "Space Concordia") (part "CMP-002-00085-1"))
    )
    (comp (ref "J3")
      (value "776087-1")
      (footprint "FP-776087-1-MFG")
      (description "CONN HEADER R/A 23POS 4MM")
      (libsource (lib "Altium Content Vault") (part "1cdbe6524175775e54446a79a4f0ed8"))
    )
    (comp (ref "J4")
      (value "FM4-NZRP-PCB-1")
      (footprint "FM4-NZRP-PCB-1-Footprint-1")
      (description "Connector RF Mini-FAKRA Plug 9GHz 50Ohm Solder Right Angle Through Hole")
      (libsource (lib "Space Concordia") (part "CMP-002-00085-1"))
    )
    (comp (ref "J5")
      (value "47659-1100")
      (footprint "FP-47659-1100-MFG")
      (description "HDMI Connector, 19 Contact(s), Female, Straight, Surface Mount Terminal, Locking, Receptacle")
      (libsource (lib "Space Concordia") (part "47659-1100"))
    )
    (comp (ref "J6")
      (value "10118193-0001LF")
      (footprint "FCI-10118193-0001LF-5_V")
      (description "Micro USB B Type Receptacle, -55 to 85 degC, 5-Pin SMD, RoHS, Tape and Reel")
      (fields (field (name "MANUFACTURER") "FCI"))
      (libsource (lib "Altium Content Vault") (part "USB-5-6SHLD"))
    )
    (comp (ref "J7")
      (value "HTSW-104-07-G-S")
      (footprint "FP-HTSW-104-07-G-S-MFG")
      (description "CONN HEADER VERT 4POS 2.54MM")
      (libsource (lib "") (part "299a8cea1bdcbc3624fe62c390fa72c_1"))
    )
    (comp (ref "J8")
      (value "99S23F-40MA5-Z")
      (footprint "FP-99S23F-40MA5-Z-MFG")
      (description "HSD(M), R/A, 2GHz, 100Ohms, PCB, Solder, Thru-Hole, Tin, Gold, Keyed/Coded, Water Blue")
      (libsource (lib "Space Concordia") (part "99S23F-40MA5-Z"))
    )
    (comp (ref "J9")
      (value "47053-1000")
      (footprint "FP-470531000-MFG")
      (description "CONN HEADER VERT 4POS 2.54MM")
      (libsource (lib "Altium Content Vault") (part "299a8cea1bdcbc3624fe62c390fa72c"))
    )
    (comp (ref "J10")
      (value "5-2301995-4")
      (footprint "FP-5-2301995-4-MFG")
      (description "CONN JACK 1PORT 1000 BASE-T PCB")
      (libsource (lib "Altium Content Vault") (part "0805b62904d83b460e670db7b39b4f8"))
    )
    (comp (ref "J11")
      (value "47053-1000")
      (footprint "FP-470531000-MFG")
      (description "CONN HEADER VERT 4POS 2.54MM")
      (libsource (lib "Altium Content Vault") (part "299a8cea1bdcbc3624fe62c390fa72c"))
    )
    (comp (ref "J12")
      (value "629104190121")
      (footprint "629104190121")
      (description "WR-COM_USB_Type A_Horizontal_SMT_ShortType")
      (libsource (lib "Altium Content Vault") (part "USB 2.0_Type A_Receptacle_1 Port"))
    )
    (comp (ref "MH1")
      (value "PTHV6")
      (footprint "PTHV6 M2")
      (libsource (lib "Space Concordia") (part "PTHV6"))
    )
    (comp (ref "MH2")
      (value "PTHV6")
      (footprint "PTHV6 M2")
      (libsource (lib "Space Concordia") (part "PTHV6"))
    )
    (comp (ref "MH3")
      (value "PTHV6")
      (footprint "PTHV6 M2")
      (libsource (lib "Space Concordia") (part "PTHV6"))
    )
    (comp (ref "MH4")
      (value "PTHV6")
      (footprint "PTHV6 M2")
      (libsource (lib "Space Concordia") (part "PTHV6"))
    )
    (comp (ref "MH5")
      (value "PTHV6")
      (footprint "PTHV6 M2")
      (libsource (lib "Space Concordia") (part "PTHV6"))
    )
    (comp (ref "MH6")
      (value "PTHV6")
      (footprint "PTHV6 M2")
      (libsource (lib "Space Concordia") (part "PTHV6"))
    )
    (comp (ref "MH7")
      (value "PTHV6")
      (footprint "PTHV6 M2")
      (libsource (lib "Space Concordia") (part "PTHV6"))
    )
    (comp (ref "MH8")
      (value "PTHV6")
      (footprint "PTHV6 M2")
      (libsource (lib "Space Concordia") (part "PTHV6"))
    )
    (comp (ref "MH9")
      (value "PTHV6")
      (footprint "PTHV6 M2")
      (libsource (lib "Space Concordia") (part "PTHV6"))
    )
    (comp (ref "MH10")
      (value "PTHV6")
      (footprint "PTHV6 M2")
      (libsource (lib "Space Concordia") (part "PTHV6"))
    )
    (comp (ref "MH11")
      (value "PTHV6")
      (footprint "PTHV6 M2")
      (libsource (lib "Space Concordia") (part "PTHV6"))
    )
    (comp (ref "MH12")
      (value "PTHV6")
      (footprint "PTHV6 M2")
      (libsource (lib "Space Concordia") (part "PTHV6"))
    )
    (comp (ref "Q23")
      (value "DMN2710UVQ-13")
      (footprint "SOTFL50P162X60-6N")
      (description "MOSFET Array, Dual N Channel, 20 V, 920 mA, 450 Milliohms, SOT-563, 6 Pins")
      (libsource (lib "Space Concordia") (part "DMN2710UVQ-13"))
    )
    (comp (ref "Q24")
      (value "DMN2710UVQ-13")
      (footprint "SOTFL50P162X60-6N")
      (description "MOSFET Array, Dual N Channel, 20 V, 920 mA, 450 Milliohms, SOT-563, 6 Pins")
      (libsource (lib "Space Concordia") (part "DMN2710UVQ-13"))
    )
    (comp (ref "Q25")
      (value "DMN2710UVQ-13")
      (footprint "SOTFL50P162X60-6N")
      (description "MOSFET Array, Dual N Channel, 20 V, 920 mA, 450 Milliohms, SOT-563, 6 Pins")
      (libsource (lib "Space Concordia") (part "DMN2710UVQ-13"))
    )
    (comp (ref "Q26")
      (value "BSS138W-7-F")
      (footprint "DIOD-SOT323-3_V")
      (fields (field (name "MANUFACTURER") "DiodesIncorporated"))
      (libsource (lib "Altium Content Vault") (part "NEMOS-GSD-3"))
    )
    (comp (ref "Q27")
      (value "DMN2710UVQ-13")
      (footprint "SOTFL50P162X60-6N")
      (description "MOSFET Array, Dual N Channel, 20 V, 920 mA, 450 Milliohms, SOT-563, 6 Pins")
      (libsource (lib "Space Concordia") (part "DMN2710UVQ-13"))
    )
    (comp (ref "Q28")
      (value "DMN2710UVQ-13")
      (footprint "SOTFL50P162X60-6N")
      (description "MOSFET Array, Dual N Channel, 20 V, 920 mA, 450 Milliohms, SOT-563, 6 Pins")
      (libsource (lib "Space Concordia") (part "DMN2710UVQ-13"))
    )
    (comp (ref "R138")
      (value "100k")
      (footprint "R0603B")
      (description "Resistor")
      (libsource (lib "Space Concordia") (part "Resistor"))
    )
    (comp (ref "R139")
      (value "100k")
      (footprint "R0603B")
      (description "Resistor")
      (libsource (lib "Space Concordia") (part "Resistor"))
    )
    (comp (ref "R140")
      (value "100k")
      (footprint "R0603B")
      (description "Resistor")
      (libsource (lib "Space Concordia") (part "Resistor"))
    )
    (comp (ref "R141")
      (value "100k")
      (footprint "R0603B")
      (description "Resistor")
      (libsource (lib "Space Concordia") (part "Resistor"))
    )
    (comp (ref "R142")
      (value "100k")
      (footprint "R0603B")
      (description "Resistor")
      (libsource (lib "Space Concordia") (part "Resistor"))
    )
    (comp (ref "R143")
      (value "10k")
      (footprint "R0603B")
      (description "Resistor")
      (libsource (lib "Space Concordia") (part "Resistor"))
    )
    (comp (ref "R144")
      (value "1M")
      (footprint "R0603B")
      (description "Resistor")
      (libsource (lib "Space Concordia") (part "Resistor"))
    )
    (comp (ref "R145")
      (value "1k")
      (footprint "R0603B")
      (description "Resistor")
      (libsource (lib "Space Concordia") (part "Resistor"))
    )
    (comp (ref "R146")
      (value "ERT-J1VR103J")
      (footprint "RESC1608X90X30ML15T20")
      (fields (field (name "MANUFACTURER") "Panasonic"))
      (libsource (lib "Altium Content Vault") (part "RES"))
    )
    (comp (ref "R147")
      (value "100k")
      (footprint "R0603B")
      (description "Resistor")
      (libsource (lib "Space Concordia") (part "Resistor"))
    )
    (comp (ref "R148")
      (value "100k")
      (footprint "R0603B")
      (description "Resistor")
      (libsource (lib "Space Concordia") (part "Resistor"))
    )
    (comp (ref "R149")
      (value "1k")
      (footprint "R0603B")
      (description "Resistor")
      (libsource (lib "Space Concordia") (part "Resistor"))
    )
    (comp (ref "R150")
      (value "100k")
      (footprint "R0603B")
      (description "Resistor")
      (libsource (lib "Space Concordia") (part "Resistor"))
    )
    (comp (ref "R151")
      (value "0402 JUMPER")
      (footprint "RESC1005X40X25ML05T05")
      (description "READ THE NAME")
      (libsource (lib "Space Concordia") (part "CMP-009-00206-2"))
    )
    (comp (ref "R152")
      (value "0402 JUMPER")
      (footprint "RESC1005X40X25ML05T05")
      (description "READ THE NAME")
      (libsource (lib "Space Concordia") (part "CMP-009-00206-2"))
    )
    (comp (ref "R153")
      (value "0402 JUMPER")
      (footprint "RESC1005X40X25ML05T05")
      (description "READ THE NAME")
      (libsource (lib "Space Concordia") (part "CMP-009-00206-2"))
    )
    (comp (ref "R154")
      (value "0402 JUMPER")
      (footprint "RESC1005X40X25ML05T05")
      (description "READ THE NAME")
      (libsource (lib "Space Concordia") (part "CMP-009-00206-2"))
    )
    (comp (ref "R155")
      (value "0402 JUMPER")
      (footprint "RESC1005X40X25ML05T05")
      (description "READ THE NAME")
      (libsource (lib "Space Concordia") (part "CMP-009-00206-2"))
    )
    (comp (ref "R156")
      (value "0402 JUMPER")
      (footprint "RESC1005X40X25ML05T05")
      (description "READ THE NAME")
      (libsource (lib "Space Concordia") (part "CMP-009-00206-2"))
    )
    (comp (ref "R157")
      (value "0402 JUMPER")
      (footprint "RESC1005X40X25ML05T05")
      (description "READ THE NAME")
      (libsource (lib "Space Concordia") (part "CMP-009-00206-2"))
    )
    (comp (ref "R158")
      (value "0402 JUMPER")
      (footprint "RESC1005X40X25ML05T05")
      (description "READ THE NAME")
      (libsource (lib "Space Concordia") (part "CMP-009-00206-2"))
    )
    (comp (ref "R164")
      (value "1k")
      (footprint "R0603B")
      (description "Resistor")
      (libsource (lib "Space Concordia") (part "Resistor"))
    )
    (comp (ref "R165")
      (value "100k")
      (footprint "R0603B")
      (description "Resistor")
      (libsource (lib "Space Concordia") (part "Resistor"))
    )
    (comp (ref "R166")
      (value "0402 JUMPER")
      (footprint "RESC1005X40X25ML05T05")
      (description "READ THE NAME")
      (libsource (lib "Space Concordia") (part "CMP-009-00206-2"))
    )
    (comp (ref "R167")
      (value "100k")
      (footprint "R0603B")
      (description "Resistor")
      (libsource (lib "Space Concordia") (part "Resistor"))
    )
    (comp (ref "R168")
      (value "100k")
      (footprint "R0603B")
      (description "Resistor")
      (fields (field (name "ALTIUM_VALUE") "100k"))
      (libsource (lib "Space Concordia") (part "Resistor"))
    )
    (comp (ref "R169")
      (value "100k")
      (footprint "R0603B")
      (description "Resistor")
      (fields (field (name "ALTIUM_VALUE") "100k"))
      (libsource (lib "Space Concordia") (part "Resistor"))
    )
    (comp (ref "R170")
      (value "100k")
      (footprint "R0603B")
      (description "Resistor")
      (fields (field (name "ALTIUM_VALUE") "100k"))
      (libsource (lib "Space Concordia") (part "Resistor"))
    )
    (comp (ref "R171")
      (value "100k")
      (footprint "R0603B")
      (description "Resistor")
      (fields (field (name "ALTIUM_VALUE") "100k"))
      (libsource (lib "Space Concordia") (part "Resistor"))
    )
    (comp (ref "R172")
      (value "1k")
      (footprint "R0603B")
      (description "Resistor")
      (libsource (lib "Space Concordia") (part "Resistor"))
    )
    (comp (ref "R173")
      (value "1k")
      (footprint "R0603B")
      (description "Resistor")
      (libsource (lib "Space Concordia") (part "Resistor"))
    )
    (comp (ref "R174")
      (value "1k")
      (footprint "R0603B")
      (description "Resistor")
      (libsource (lib "Space Concordia") (part "Resistor"))
    )
    (comp (ref "R175")
      (value "100k")
      (footprint "R0603B")
      (description "Resistor")
      (fields (field (name "ALTIUM_VALUE") "100k"))
      (libsource (lib "Space Concordia") (part "Resistor"))
    )
    (comp (ref "R176")
      (value "100k")
      (footprint "R0603B")
      (description "Resistor")
      (fields (field (name "ALTIUM_VALUE") "100k"))
      (libsource (lib "Space Concordia") (part "Resistor"))
    )
    (comp (ref "R177")
      (value "1k")
      (footprint "R0603B")
      (description "Resistor")
      (libsource (lib "Space Concordia") (part "Resistor"))
    )
    (comp (ref "R178")
      (value "1k")
      (footprint "R0603B")
      (description "Resistor")
      (libsource (lib "Space Concordia") (part "Resistor"))
    )
    (comp (ref "R179")
      (value "1k")
      (footprint "R0603B")
      (description "Resistor")
      (libsource (lib "Space Concordia") (part "Resistor"))
    )
    (comp (ref "R180")
      (value "100k")
      (footprint "R0603B")
      (description "Resistor")
      (fields (field (name "ALTIUM_VALUE") "100k"))
      (libsource (lib "Space Concordia") (part "Resistor"))
    )
    (comp (ref "R181")
      (value "100k")
      (footprint "R0603B")
      (description "Resistor")
      (fields (field (name "ALTIUM_VALUE") "100k"))
      (libsource (lib "Space Concordia") (part "Resistor"))
    )
    (comp (ref "R182")
      (value "100k")
      (footprint "R0603B")
      (description "Resistor")
      (libsource (lib "Space Concordia") (part "Resistor"))
    )
    (comp (ref "R183")
      (value "0402 JUMPER")
      (footprint "RESC1005X40X25ML05T05")
      (description "READ THE NAME")
      (libsource (lib "Space Concordia") (part "CMP-009-00206-2"))
    )
    (comp (ref "R184")
      (value "0402 JUMPER")
      (footprint "RESC1005X40X25ML05T05")
      (description "READ THE NAME")
      (libsource (lib "Space Concordia") (part "CMP-009-00206-2"))
    )
    (comp (ref "R269")
      (value "0402 JUMPER")
      (footprint "RESC1005X40X25ML05T05")
      (description "READ THE NAME")
      (libsource (lib "Space Concordia") (part "CMP-009-00206-2"))
    )
    (comp (ref "R270")
      (value "0402 JUMPER")
      (footprint "RESC1005X40X25ML05T05")
      (description "READ THE NAME")
      (libsource (lib "Space Concordia") (part "CMP-009-00206-2"))
    )
    (comp (ref "R271")
      (value "0402 JUMPER")
      (footprint "RESC1005X40X25ML05T05")
      (description "READ THE NAME")
      (libsource (lib "Space Concordia") (part "CMP-009-00206-2"))
    )
    (comp (ref "R272")
      (value "0402 JUMPER")
      (footprint "RESC1005X40X25ML05T05")
      (description "READ THE NAME")
      (libsource (lib "Space Concordia") (part "CMP-009-00206-2"))
    )
    (comp (ref "R273")
      (value "0402 JUMPER")
      (footprint "RESC1005X40X25ML05T05")
      (description "READ THE NAME")
      (libsource (lib "Space Concordia") (part "CMP-009-00206-2"))
    )
    (comp (ref "R274")
      (value "0402 JUMPER")
      (footprint "RESC1005X40X25ML05T05")
      (description "READ THE NAME")
      (libsource (lib "Space Concordia") (part "CMP-009-00206-2"))
    )
    (comp (ref "R275")
      (value "0402 JUMPER")
      (footprint "RESC1005X40X25ML05T05")
      (description "READ THE NAME")
      (libsource (lib "Space Concordia") (part "CMP-009-00206-2"))
    )
    (comp (ref "R276")
      (value "0402 JUMPER")
      (footprint "RESC1005X40X25ML05T05")
      (description "READ THE NAME")
      (libsource (lib "Space Concordia") (part "CMP-009-00206-2"))
    )
    (comp (ref "R277")
      (value "0402 JUMPER")
      (footprint "RESC1005X40X25ML05T05")
      (description "READ THE NAME")
      (libsource (lib "Space Concordia") (part "CMP-009-00206-2"))
    )
    (comp (ref "R278")
      (value "0402 JUMPER")
      (footprint "RESC1005X40X25ML05T05")
      (description "READ THE NAME")
      (libsource (lib "Space Concordia") (part "CMP-009-00206-2"))
    )
    (comp (ref "R279")
      (value "0402 JUMPER")
      (footprint "RESC1005X40X25ML05T05")
      (description "READ THE NAME")
      (libsource (lib "Space Concordia") (part "CMP-009-00206-2"))
    )
    (comp (ref "R280")
      (value "0402 JUMPER")
      (footprint "RESC1005X40X25ML05T05")
      (description "READ THE NAME")
      (libsource (lib "Space Concordia") (part "CMP-009-00206-2"))
    )
    (comp (ref "TP1")
      (value "TPAD6R")
      (footprint "New footprint 1")
      (description "Test Point .6mm")
      (libsource (lib "Space Concordia") (part "TP"))
    )
    (comp (ref "TP2")
      (value "TPAD6R")
      (footprint "New footprint 1")
      (description "Test Point .6mm")
      (libsource (lib "Space Concordia") (part "TP"))
    )
    (comp (ref "TP3")
      (value "TPAD6R")
      (footprint "New footprint 1")
      (description "Test Point .6mm")
      (libsource (lib "Space Concordia") (part "TP"))
    )
    (comp (ref "TP4")
      (value "TPAD6R")
      (footprint "New footprint 1")
      (description "Test Point .6mm")
      (libsource (lib "Space Concordia") (part "TP"))
    )
    (comp (ref "TP5")
      (value "TPAD6R")
      (footprint "New footprint 1")
      (description "Test Point .6mm")
      (libsource (lib "Space Concordia") (part "TP"))
    )
    (comp (ref "TP6")
      (value "TPAD6R")
      (footprint "New footprint 1")
      (description "Test Point .6mm")
      (libsource (lib "Space Concordia") (part "TP"))
    )
    (comp (ref "TP7")
      (value "TPAD6R")
      (footprint "New footprint 1")
      (description "Test Point .6mm")
      (libsource (lib "Space Concordia") (part "TP"))
    )
    (comp (ref "TP8")
      (value "TPAD6R")
      (footprint "New footprint 1")
      (description "Test Point .6mm")
      (libsource (lib "Space Concordia") (part "TP"))
    )
    (comp (ref "U15")
      (value "AP22804AW5-7")
      (footprint "SOT95P285X140-5N")
      (description "SINGLE CHANNEL POWER DISTRIBUTION LOAD SWITCH, -40 to 85°C pF, RoHS")
      (libsource (lib "Space Concordia") (part "AP22804AW5-7"))
    )
    (comp (ref "U16")
      (value "AP22804AW5-7")
      (footprint "SOT95P285X140-5N")
      (description "SINGLE CHANNEL POWER DISTRIBUTION LOAD SWITCH, -40 to 85°C pF, RoHS")
      (libsource (lib "Space Concordia") (part "AP22804AW5-7"))
    )
    (comp (ref "U17")
      (value "AP22804AW5-7")
      (footprint "SOT95P285X140-5N")
      (description "SINGLE CHANNEL POWER DISTRIBUTION LOAD SWITCH, -40 to 85°C pF, RoHS")
      (libsource (lib "") (part "AP22804AW5-7_1"))
    )
    (comp (ref "U18")
      (value "NC7SZ125M5X")
      (footprint "FAIR-SOT23-5_V")
      (fields (field (name "MANUFACTURER") "Fairchild Semiconductor"))
      (libsource (lib "Altium Content Vault") (part "FAIR-NC7SZ125-SOT23-5"))
    )
    (comp (ref "U19")
      (value "AP22804AW5-7")
      (footprint "SOT95P285X140-5N")
      (description "SINGLE CHANNEL POWER DISTRIBUTION LOAD SWITCH, -40 to 85°C pF, RoHS")
      (libsource (lib "Space Concordia") (part "AP22804AW5-7"))
    )
    (comp (ref "U20")
      (value "DNP/NC7SZ125M5X")
      (footprint "FAIR-SOT23-5_V")
      (fields (field (name "MANUFACTURER") "Fairchild Semiconductor"))
      (libsource (lib "") (part "FAIR-NC7SZ125-SOT23-5_1"))
    )
  )
  (nets
    (net (code "7") (name "/1V8_CPU_FAN_PWM") (class "Default")
      (node (ref "R178") (pin "2") (pinfunction "2_2") (pintype "passive"))
    )
    (net (code "8") (name "/1V8_CPU_FAN_TACH") (class "Default")
      (node (ref "R172") (pin "2") (pinfunction "2_2") (pintype "passive"))
    )
    (net (code "12") (name "/1V8_GPIO01") (class "Default")
      (node (ref "TP3") (pin "1") (pinfunction "TP_1") (pintype "passive"))
    )
    (net (code "13") (name "/1V8_GPIO04") (class "Default")
      (node (ref "TP4") (pin "1") (pinfunction "TP_1") (pintype "passive"))
    )
    (net (code "14") (name "/1V8_GPIO06") (class "Default")
      (node (ref "TP5") (pin "1") (pinfunction "TP_1") (pintype "passive"))
    )
    (net (code "15") (name "/1V8_GPIO07_PWM") (class "Default")
      (node (ref "R173") (pin "2") (pinfunction "2_2") (pintype "passive"))
    )
    (net (code "16") (name "/1V8_GPIO09") (class "Default")
      (node (ref "TP6") (pin "1") (pinfunction "TP_1") (pintype "passive"))
    )
    (net (code "17") (name "/1V8_GPIO11") (class "Default")
      (node (ref "TP7") (pin "1") (pinfunction "TP_1") (pintype "passive"))
    )
    (net (code "18") (name "/1V8_GPIO12") (class "Default")
      (node (ref "TP8") (pin "1") (pinfunction "TP_1") (pintype "passive"))
    )
    (net (code "19") (name "/1V8_GPIO13_PWM") (class "Default")
      (node (ref "R179") (pin "2") (pinfunction "2_2") (pintype "passive"))
    )
    (net (code "36") (name "/1V8_nM2_ALERT") (class "Default")
      (node (ref "U20") (pin "4") (pinfunction "Y_4") (pintype "tri_state"))
    )
    (net (code "39") (name "/1V8_nSYS_RESET") (class "Default")
      (node (ref "R143") (pin "1") (pinfunction "1_1") (pintype "passive"))
      (node (ref "R144") (pin "2") (pinfunction "2_2") (pintype "passive"))
      (node (ref "U17") (pin "4") (pinfunction "EN_4") (pintype "input"))
    )
    (net (code "40") (name "/1V8_nUSB0_VBUS_DET") (class "Default")
      (node (ref "R166") (pin "2") (pinfunction "2_2") (pintype "passive"))
    )
    (net (code "73") (name "/3V3_HPD") (class "Default")
      (node (ref "R280") (pin "2") (pinfunction "2_2") (pintype "passive"))
    )
    (net (code "76") (name "/3V3_I2C1_SCL") (class "Default")
      (node (ref "TP2") (pin "1") (pinfunction "TP_1") (pintype "passive"))
    )
    (net (code "77") (name "/3V3_I2C1_SDA") (class "Default")
      (node (ref "TP1") (pin "1") (pinfunction "TP_1") (pintype "passive"))
    )
    (net (code "106") (name "/3V3_MODULE_ID") (class "Default")
      (node (ref "U18") (pin "2") (pinfunction "A_2") (pintype "input"))
    )
    (net (code "118") (name "/3V3_UART2_RXD") (class "Default")
      (node (ref "J7") (pin "4") (pinfunction "4_4") (pintype "passive"))
    )
    (net (code "119") (name "/3V3_UART2_TXD") (class "Default")
      (node (ref "J7") (pin "3") (pinfunction "3_3") (pintype "passive"))
    )
    (net (code "120") (name "/3V3_USB_PWR_EN") (class "Default")
      (node (ref "U19") (pin "4") (pinfunction "EN_4") (pintype "input"))
    )
    (net (code "125") (name "/3V3_nSYS_RESET") (class "Default")
      (node (ref "R149") (pin "2") (pinfunction "2_2") (pintype "passive"))
      (node (ref "U17") (pin "1") (pinfunction "VOUT_1") (pintype "power_in"))
    )
    (net (code "127") (name "/5V0_DBG_USB_VBUS") (class "Default")
      (node (ref "C156") (pin "1") (pinfunction "1_1") (pintype "passive"))
      (node (ref "D23") (pin "4") (pinfunction "IO3_4") (pintype "bidirectional"))
      (node (ref "J6") (pin "1") (pinfunction "VBUS_1") (pintype "passive"))
      (node (ref "Q26") (pin "1") (pinfunction "G_1") (pintype "passive"))
      (node (ref "R167") (pin "2") (pinfunction "2_2") (pintype "passive"))
    )
    (net (code "129") (name "/5V0_POWER_EN") (class "Default")
      (node (ref "R138") (pin "2") (pinfunction "2_2") (pintype "passive"))
      (node (ref "U15") (pin "1") (pinfunction "VOUT_1") (pintype "power_in"))
    )
    (net (code "130") (name "/5V0_SLEEP{slash}nWAKE") (class "Default")
      (node (ref "R140") (pin "2") (pinfunction "2_2") (pintype "passive"))
      (node (ref "U16") (pin "1") (pinfunction "VOUT_1") (pintype "power_in"))
    )
    (net (code "131") (name "/5V0_nSHDN_REQ") (class "Default")
      (node (ref "D14") (pin "1") (pinfunction "C_1") (pintype "passive"))
    )
    (net (code "136") (name "/AMBIENT_TEMP") (class "Default")
      (node (ref "R145") (pin "1") (pinfunction "1_1") (pintype "passive"))
      (node (ref "R146") (pin "2") (pinfunction "2_2") (pintype "passive"))
    )
    (net (code "137") (name "/CAN_N") (class "Default")
      (node (ref "J3") (pin "23") (pinfunction "23_23") (pintype "passive"))
    )
    (net (code "138") (name "/CAN_P") (class "Default")
      (node (ref "J3") (pin "22") (pinfunction "22_22") (pintype "passive"))
    )
    (net (code "159") (name "/DDC_SCK") (class "Default")
      (node (ref "R278") (pin "2") (pinfunction "2_2") (pintype "passive"))
    )
    (net (code "160") (name "/DDC_SDA") (class "Default")
      (node (ref "R277") (pin "2") (pinfunction "2_2") (pintype "passive"))
    )
    (net (code "169") (name "/ETH_MDI0_N") (class "Default")
      (node (ref "D27") (pin "2") (pinfunction "IO2_2") (pintype "bidirectional"))
      (node (ref "J10") (pin "P2") (pinfunction "P2_P2") (pintype "passive"))
    )
    (net (code "170") (name "/ETH_MDI0_P") (class "Default")
      (node (ref "D27") (pin "1") (pinfunction "IO1_1") (pintype "bidirectional"))
      (node (ref "J10") (pin "P1") (pinfunction "P1_P1") (pintype "passive"))
    )
    (net (code "171") (name "/ETH_MDI1_N") (class "Default")
      (node (ref "D27") (pin "5") (pinfunction "IO4_5") (pintype "bidirectional"))
      (node (ref "J10") (pin "P4") (pinfunction "P4_P4") (pintype "passive"))
    )
    (net (code "172") (name "/ETH_MDI1_P") (class "Default")
      (node (ref "D27") (pin "4") (pinfunction "IO3_4") (pintype "bidirectional"))
      (node (ref "J10") (pin "P3") (pinfunction "P3_P3") (pintype "passive"))
    )
    (net (code "173") (name "/ETH_MDI2_N") (class "Default")
      (node (ref "D28") (pin "2") (pinfunction "IO2_2") (pintype "bidirectional"))
      (node (ref "J10") (pin "P8") (pinfunction "P8_P8") (pintype "passive"))
    )
    (net (code "174") (name "/ETH_MDI2_P") (class "Default")
      (node (ref "D28") (pin "1") (pinfunction "IO1_1") (pintype "bidirectional"))
      (node (ref "J10") (pin "P7") (pinfunction "P7_P7") (pintype "passive"))
    )
    (net (code "175") (name "/ETH_MDI3_N") (class "Default")
      (node (ref "D28") (pin "5") (pinfunction "IO4_5") (pintype "bidirectional"))
      (node (ref "J10") (pin "P10") (pinfunction "P10_P10") (pintype "passive"))
    )
    (net (code "176") (name "/ETH_MDI3_P") (class "Default")
      (node (ref "D28") (pin "4") (pinfunction "IO3_4") (pintype "bidirectional"))
      (node (ref "J10") (pin "P9") (pinfunction "P9_P9") (pintype "passive"))
    )
    (net (code "177") (name "/FAN_0_PWM") (class "Default")
      (node (ref "J9") (pin "4") (pinfunction "4_4") (pintype "passive"))
      (node (ref "Q27") (pin "3") (pinfunction "Drain2_3") (pintype "passive"))
      (node (ref "R175") (pin "1") (pinfunction "1_1") (pintype "passive"))
    )
    (net (code "178") (name "/FAN_0_TACH") (class "Default")
      (node (ref "J9") (pin "3") (pinfunction "3_3") (pintype "passive"))
      (node (ref "Q27") (pin "6") (pinfunction "Drain1_6") (pintype "passive"))
      (node (ref "R168") (pin "1") (pinfunction "1_1") (pintype "passive"))
    )
    (net (code "179") (name "/FAN_1_PWM") (class "Default")
      (node (ref "J11") (pin "4") (pinfunction "4_4") (pintype "passive"))
      (node (ref "Q28") (pin "3") (pinfunction "Drain2_3") (pintype "passive"))
      (node (ref "R176") (pin "1") (pinfunction "1_1") (pintype "passive"))
    )
    (net (code "180") (name "/FAN_1_TACH") (class "Default")
      (node (ref "J11") (pin "3") (pinfunction "3_3") (pintype "passive"))
      (node (ref "Q28") (pin "6") (pinfunction "Drain1_6") (pintype "passive"))
      (node (ref "R169") (pin "1") (pinfunction "1_1") (pintype "passive"))
    )
    (net (code "181") (name "/HDMI_5V") (class "Default")
      (node (ref "D21") (pin "2") (pinfunction "IO2_2") (pintype "bidirectional"))
      (node (ref "D21") (pin "9") (pinfunction "NC_9") (pintype "passive"))
      (node (ref "J5") (pin "18") (pinfunction "5V_18") (pintype "power_in"))
      (node (ref "R279") (pin "1") (pinfunction "1_1") (pintype "passive"))
    )
    (net (code "182") (name "/HDMI_5V_1") (class "Default")
      (node (ref "R279") (pin "2") (pinfunction "2_2") (pintype "passive"))
    )
    (net (code "183") (name "/HDMI_CEC") (class "Default")
      (node (ref "J5") (pin "13") (pinfunction "CEC_13") (pintype "bidirectional"))
    )
    (net (code "184") (name "/HDMI_CLK_N") (class "Default")
      (node (ref "R158") (pin "1") (pinfunction "1_1") (pintype "passive"))
      (node (ref "R276") (pin "1") (pinfunction "1_1") (pintype "passive"))
    )
    (net (code "185") (name "/HDMI_CLK_P") (class "Default")
      (node (ref "R157") (pin "1") (pinfunction "1_1") (pintype "passive"))
      (node (ref "R275") (pin "1") (pinfunction "1_1") (pintype "passive"))
    )
    (net (code "186") (name "/HDMI_D0_N") (class "Default")
      (node (ref "R156") (pin "1") (pinfunction "1_1") (pintype "passive"))
      (node (ref "R270") (pin "1") (pinfunction "1_1") (pintype "passive"))
    )
    (net (code "187") (name "/HDMI_D0_P") (class "Default")
      (node (ref "R155") (pin "1") (pinfunction "1_1") (pintype "passive"))
      (node (ref "R269") (pin "1") (pinfunction "1_1") (pintype "passive"))
    )
    (net (code "188") (name "/HDMI_D1_N") (class "Default")
      (node (ref "R154") (pin "1") (pinfunction "1_1") (pintype "passive"))
      (node (ref "R272") (pin "1") (pinfunction "1_1") (pintype "passive"))
    )
    (net (code "189") (name "/HDMI_D1_P") (class "Default")
      (node (ref "R153") (pin "1") (pinfunction "1_1") (pintype "passive"))
      (node (ref "R271") (pin "1") (pinfunction "1_1") (pintype "passive"))
    )
    (net (code "190") (name "/HDMI_D2_N") (class "Default")
      (node (ref "R152") (pin "1") (pinfunction "1_1") (pintype "passive"))
      (node (ref "R274") (pin "1") (pinfunction "1_1") (pintype "passive"))
    )
    (net (code "191") (name "/HDMI_D2_P") (class "Default")
      (node (ref "R151") (pin "1") (pinfunction "1_1") (pintype "passive"))
      (node (ref "R273") (pin "1") (pinfunction "1_1") (pintype "passive"))
    )
    (net (code "192") (name "/HDMI_HP_DET") (class "Default")
      (node (ref "D21") (pin "1") (pinfunction "IO1_1") (pintype "bidirectional"))
      (node (ref "D21") (pin "10") (pinfunction "NC_10") (pintype "passive"))
      (node (ref "J5") (pin "19") (pinfunction "HOTPLUG_19") (pintype "output"))
      (node (ref "R280") (pin "1") (pinfunction "1_1") (pintype "passive"))
    )
    (net (code "193") (name "/HDMI_SCL") (class "Default")
      (node (ref "D21") (pin "5") (pinfunction "IO4_5") (pintype "bidirectional"))
      (node (ref "D21") (pin "6") (pinfunction "NC_6") (pintype "passive"))
      (node (ref "J5") (pin "15") (pinfunction "SCL_15") (pintype "input"))
      (node (ref "R278") (pin "1") (pinfunction "1_1") (pintype "passive"))
    )
    (net (code "194") (name "/HDMI_SDA") (class "Default")
      (node (ref "D21") (pin "4") (pinfunction "IO3_4") (pintype "bidirectional"))
      (node (ref "D21") (pin "7") (pinfunction "NC_7") (pintype "passive"))
      (node (ref "J5") (pin "16") (pinfunction "SDA_16") (pintype "bidirectional"))
      (node (ref "R277") (pin "1") (pinfunction "1_1") (pintype "passive"))
    )
    (net (code "196") (name "/HV_SYS_RESET") (class "Default")
      (node (ref "Q24") (pin "2") (pinfunction "Gate1_2") (pintype "passive"))
      (node (ref "Q24") (pin "5") (pinfunction "Gate2_5") (pintype "passive"))
      (node (ref "Q25") (pin "5") (pinfunction "Gate2_5") (pintype "passive"))
      (node (ref "Q25") (pin "6") (pinfunction "Drain1_6") (pintype "passive"))
      (node (ref "R148") (pin "1") (pinfunction "1_1") (pintype "passive"))
    )
    (net (code "197") (name "/IN_CK_N") (class "Default")
      (node (ref "R276") (pin "2") (pinfunction "2_2") (pintype "passive"))
    )
    (net (code "198") (name "/IN_CK_P") (class "Default")
      (node (ref "R275") (pin "2") (pinfunction "2_2") (pintype "passive"))
    )
    (net (code "199") (name "/IN_D0_N") (class "Default")
      (node (ref "R270") (pin "2") (pinfunction "2_2") (pintype "passive"))
    )
    (net (code "200") (name "/IN_D0_P") (class "Default")
      (node (ref "R269") (pin "2") (pinfunction "2_2") (pintype "passive"))
    )
    (net (code "201") (name "/IN_D1_N") (class "Default")
      (node (ref "R272") (pin "2") (pinfunction "2_2") (pintype "passive"))
    )
    (net (code "202") (name "/IN_D1_P") (class "Default")
      (node (ref "R271") (pin "2") (pinfunction "2_2") (pintype "passive"))
    )
    (net (code "203") (name "/IN_D2_N") (class "Default")
      (node (ref "R274") (pin "2") (pinfunction "2_2") (pintype "passive"))
    )
    (net (code "204") (name "/IN_D2_P") (class "Default")
      (node (ref "R273") (pin "2") (pinfunction "2_2") (pintype "passive"))
    )
    (net (code "205") (name "/OD_ETH_LED_ACT") (class "Default")
      (node (ref "J10") (pin "P13") (pinfunction "2_ANODE_GREEN/2_CATHODE_YELLOW_P13") (pintype "passive"))
    )
    (net (code "206") (name "/OD_ETH_LED_LINK") (class "Default")
      (node (ref "J10") (pin "P12") (pinfunction "1_CATHODE_GREEN/1_ANODE_YELLOW_P12") (pintype "passive"))
    )
    (net (code "215") (name "/P1_CK_N") (class "Default")
      (node (ref "D20") (pin "1") (pinfunction "IO1_1") (pintype "bidirectional"))
      (node (ref "D20") (pin "10") (pinfunction "NC_10") (pintype "passive"))
      (node (ref "J5") (pin "12") (pinfunction "CK_N_12") (pintype "input"))
      (node (ref "R158") (pin "2") (pinfunction "2_2") (pintype "passive"))
    )
    (net (code "216") (name "/P1_CK_P") (class "Default")
      (node (ref "D20") (pin "2") (pinfunction "IO2_2") (pintype "bidirectional"))
      (node (ref "D20") (pin "9") (pinfunction "NC_9") (pintype "passive"))
      (node (ref "J5") (pin "10") (pinfunction "CK_P_10") (pintype "input"))
      (node (ref "R157") (pin "2") (pinfunction "2_2") (pintype "passive"))
    )
    (net (code "217") (name "/P1_D0_N") (class "Default")
      (node (ref "D20") (pin "4") (pinfunction "IO3_4") (pintype "bidirectional"))
      (node (ref "D20") (pin "7") (pinfunction "NC_7") (pintype "passive"))
      (node (ref "J5") (pin "9") (pinfunction "D0_N_9") (pintype "input"))
      (node (ref "R156") (pin "2") (pinfunction "2_2") (pintype "passive"))
    )
    (net (code "218") (name "/P1_D0_P") (class "Default")
      (node (ref "D20") (pin "5") (pinfunction "IO4_5") (pintype "bidirectional"))
      (node (ref "D20") (pin "6") (pinfunction "NC_6") (pintype "passive"))
      (node (ref "J5") (pin "7") (pinfunction "D0_P_7") (pintype "input"))
      (node (ref "R155") (pin "2") (pinfunction "2_2") (pintype "passive"))
    )
    (net (code "219") (name "/P1_D1_N") (class "Default")
      (node (ref "D19") (pin "1") (pinfunction "IO1_1") (pintype "bidirectional"))
      (node (ref "D19") (pin "10") (pinfunction "NC_10") (pintype "passive"))
      (node (ref "J5") (pin "6") (pinfunction "D1_N_6") (pintype "input"))
      (node (ref "R154") (pin "2") (pinfunction "2_2") (pintype "passive"))
    )
    (net (code "220") (name "/P1_D1_P") (class "Default")
      (node (ref "D19") (pin "2") (pinfunction "IO2_2") (pintype "bidirectional"))
      (node (ref "D19") (pin "9") (pinfunction "NC_9") (pintype "passive"))
      (node (ref "J5") (pin "4") (pinfunction "D1_P_4") (pintype "input"))
      (node (ref "R153") (pin "2") (pinfunction "2_2") (pintype "passive"))
    )
    (net (code "221") (name "/P1_D2_N") (class "Default")
      (node (ref "D19") (pin "4") (pinfunction "IO3_4") (pintype "bidirectional"))
      (node (ref "D19") (pin "7") (pinfunction "NC_7") (pintype "passive"))
      (node (ref "J5") (pin "3") (pinfunction "D2_N_3") (pintype "input"))
      (node (ref "R152") (pin "2") (pinfunction "2_2") (pintype "passive"))
    )
    (net (code "222") (name "/P1_D2_P") (class "Default")
      (node (ref "D19") (pin "5") (pinfunction "IO4_5") (pintype "bidirectional"))
      (node (ref "D19") (pin "6") (pinfunction "NC_6") (pintype "passive"))
      (node (ref "J5") (pin "1") (pinfunction "D2_P_1") (pintype "input"))
      (node (ref "R151") (pin "2") (pinfunction "2_2") (pintype "passive"))
    )
    (net (code "245") (name "/RF_MAX96724_0_SIO_A") (class "Default")
      (node (ref "J1") (pin "2") (pinfunction "2_2") (pintype "passive"))
    )
    (net (code "246") (name "/RF_MAX96724_0_SIO_B") (class "Default")
      (node (ref "J1") (pin "1") (pinfunction "1_1") (pintype "passive"))
    )
    (net (code "247") (name "/RF_MAX96724_0_SIO_C") (class "Default")
      (node (ref "J1") (pin "4") (pinfunction "4_4") (pintype "passive"))
    )
    (net (code "248") (name "/RF_MAX96724_0_SIO_D") (class "Default")
      (node (ref "J1") (pin "3") (pinfunction "3_3") (pintype "passive"))
    )
    (net (code "249") (name "/RF_MAX96724_1_SIO_A") (class "Default")
      (node (ref "J4") (pin "2") (pinfunction "2_2") (pintype "passive"))
    )
    (net (code "250") (name "/RF_MAX96724_1_SIO_B") (class "Default")
      (node (ref "J4") (pin "1") (pinfunction "1_1") (pintype "passive"))
    )
    (net (code "251") (name "/RF_MAX96724_1_SIO_C") (class "Default")
      (node (ref "J4") (pin "4") (pinfunction "4_4") (pintype "passive"))
    )
    (net (code "252") (name "/RF_MAX96724_1_SIO_D") (class "Default")
      (node (ref "J4") (pin "3") (pinfunction "3_3") (pintype "passive"))
    )
    (net (code "253") (name "/RF_MAX96751_0_A_N") (class "Default")
      (node (ref "J8") (pin "3") (pinfunction "3_3") (pintype "passive"))
    )
    (net (code "254") (name "/RF_MAX96751_0_A_P") (class "Default")
      (node (ref "J8") (pin "1") (pinfunction "1_1") (pintype "passive"))
    )
    (net (code "255") (name "/RF_MAX96751_0_B_N") (class "Default")
      (node (ref "J8") (pin "2") (pinfunction "2_2") (pintype "passive"))
    )
    (net (code "256") (name "/RF_MAX96751_0_B_P") (class "Default")
      (node (ref "J8") (pin "4") (pinfunction "4_4") (pintype "passive"))
    )
    (net (code "257") (name "/RJ45_CT_CAP") (class "Default")
      (node (ref "C5") (pin "1") (pinfunction "1_1") (pintype "passive"))
      (node (ref "J10") (pin "P5") (pinfunction "P5_P5") (pintype "passive"))
      (node (ref "J10") (pin "P6") (pinfunction "P6_P6") (pintype "passive"))
    )
    (net (code "258") (name "/USB2_0_N") (class "Default")
      (node (ref "D23") (pin "2") (pinfunction "IO2_2") (pintype "bidirectional"))
      (node (ref "J6") (pin "2") (pinfunction "D-_2") (pintype "passive"))
    )
    (net (code "259") (name "/USB2_0_P") (class "Default")
      (node (ref "D23") (pin "1") (pinfunction "IO1_1") (pintype "bidirectional"))
      (node (ref "J6") (pin "3") (pinfunction "D+_3") (pintype "passive"))
    )
    (net (code "260") (name "/USB2_1_N") (class "Default")
      (node (ref "D29") (pin "2") (pinfunction "IO2_2") (pintype "bidirectional"))
      (node (ref "J12") (pin "2") (pinfunction "D-_2") (pintype "passive"))
    )
    (net (code "261") (name "/USB2_1_P") (class "Default")
      (node (ref "D29") (pin "4") (pinfunction "IO3_4") (pintype "bidirectional"))
      (node (ref "J12") (pin "3") (pinfunction "D+_3") (pintype "passive"))
    )
    (net (code "262") (name "/USB2_1_TYPEA_5V") (class "Default")
      (node (ref "D29") (pin "1") (pinfunction "IO1_1") (pintype "bidirectional"))
      (node (ref "J12") (pin "1") (pinfunction "VBUS_1") (pintype "passive"))
      (node (ref "U19") (pin "1") (pinfunction "VOUT_1") (pintype "power_in"))
    )
    (net (code "271") (name "/nNVME_M2_ALERT") (class "Default")
      (node (ref "R184") (pin "2") (pinfunction "2_2") (pintype "passive"))
    )
    (net (code "272") (name "/nWIFI_M2_ALERT") (class "Default")
      (node (ref "R183") (pin "2") (pinfunction "2_2") (pintype "passive"))
    )
    (net (code "273") (name "3V3_DES_0") (class "Default")
      (node (ref "F16") (pin "2") (pinfunction "2_2") (pintype "passive"))
    )
    (net (code "274") (name "3V3_DES_1") (class "Default")
      (node (ref "F17") (pin "2") (pinfunction "2_2") (pintype "passive"))
    )
    (net (code "275") (name "3V3_HDMI") (class "Default")
      (node (ref "F19") (pin "2") (pinfunction "2_2") (pintype "passive"))
    )
    (net (code "276") (name "3V3_INT") (class "Default")
      (node (ref "R142") (pin "2") (pinfunction "2_2") (pintype "passive"))
      (node (ref "R145") (pin "2") (pinfunction "2_2") (pintype "passive"))
      (node (ref "R147") (pin "2") (pinfunction "2_2") (pintype "passive"))
      (node (ref "U17") (pin "5") (pinfunction "VIN_5") (pintype "power_in"))
      (node (ref "U18") (pin "5") (pinfunction "VCC_5") (pintype "power_in"))
    )
    (net (code "277") (name "3V3_M2_NVME") (class "Default")
      (node (ref "F14") (pin "2") (pinfunction "2_2") (pintype "passive"))
    )
    (net (code "278") (name "3V3_M2_WIFI") (class "Default")
      (node (ref "F15") (pin "2") (pinfunction "2_2") (pintype "passive"))
    )
    (net (code "279") (name "3V3_MAIN") (class "Default")
      (node (ref "F14") (pin "1") (pinfunction "1_1") (pintype "passive"))
      (node (ref "F15") (pin "1") (pinfunction "1_1") (pintype "passive"))
      (node (ref "F16") (pin "1") (pinfunction "1_1") (pintype "passive"))
      (node (ref "F17") (pin "1") (pinfunction "1_1") (pintype "passive"))
      (node (ref "F18") (pin "1") (pinfunction "1_1") (pintype "passive"))
      (node (ref "F19") (pin "1") (pinfunction "1_1") (pintype "passive"))
      (node (ref "R164") (pin "1") (pinfunction "1_1") (pintype "passive"))
      (node (ref "R174") (pin "2") (pinfunction "2_2") (pintype "passive"))
      (node (ref "R177") (pin "2") (pinfunction "2_2") (pintype "passive"))
    )
    (net (code "280") (name "3V3_SER_0") (class "Default")
      (node (ref "F18") (pin "2") (pinfunction "2_2") (pintype "passive"))
    )
    (net (code "281") (name "5V0_HDMI") (class "Default")
      (node (ref "F11") (pin "2") (pinfunction "2_2") (pintype "passive"))
    )
    (net (code "283") (name "5V0_JETSON") (class "Default")
      (node (ref "F10") (pin "2") (pinfunction "2_2") (pintype "passive"))
      (node (ref "U15") (pin "5") (pinfunction "VIN_5") (pintype "power_in"))
      (node (ref "U16") (pin "5") (pinfunction "VIN_5") (pintype "power_in"))
    )
    (net (code "284") (name "5V0_MAIN") (class "Default")
      (node (ref "F10") (pin "1") (pinfunction "1_1") (pintype "passive"))
      (node (ref "F11") (pin "1") (pinfunction "1_1") (pintype "passive"))
      (node (ref "F12") (pin "1") (pinfunction "1_1") (pintype "passive"))
      (node (ref "F21") (pin "1") (pinfunction "1_1") (pintype "passive"))
      (node (ref "F22") (pin "1") (pinfunction "1_1") (pintype "passive"))
      (node (ref "R168") (pin "2") (pinfunction "2_2") (pintype "passive"))
      (node (ref "R169") (pin "2") (pinfunction "2_2") (pintype "passive"))
      (node (ref "R175") (pin "2") (pinfunction "2_2") (pintype "passive"))
      (node (ref "R176") (pin "2") (pinfunction "2_2") (pintype "passive"))
    )
    (net (code "285") (name "5V0_USB") (class "Default")
      (node (ref "F12") (pin "2") (pinfunction "2_2") (pintype "passive"))
      (node (ref "U19") (pin "5") (pinfunction "VIN_5") (pintype "power_in"))
    )
    (net (code "286") (name "12V0_JETSON") (class "Default")
      (node (ref "F9") (pin "2") (pinfunction "2_2") (pintype "passive"))
    )
    (net (code "287") (name "12V0_MAIN") (class "Default")
      (node (ref "F6") (pin "1") (pinfunction "1_1") (pintype "passive"))
      (node (ref "F7") (pin "1") (pinfunction "1_1") (pintype "passive"))
      (node (ref "F8") (pin "1") (pinfunction "1_1") (pintype "passive"))
      (node (ref "F9") (pin "1") (pinfunction "1_1") (pintype "passive"))
    )
    (net (code "288") (name "12V0_PoC_0") (class "Default")
      (node (ref "F6") (pin "2") (pinfunction "2_2") (pintype "passive"))
    )
    (net (code "289") (name "12V0_PoC_1") (class "Default")
      (node (ref "F7") (pin "2") (pinfunction "2_2") (pintype "passive"))
    )
    (net (code "290") (name "12V0_PoC_2") (class "Default")
      (node (ref "F8") (pin "2") (pinfunction "2_2") (pintype "passive"))
      (node (ref "J8") (pin "12") (pinfunction "12_12") (pintype "passive"))
    )
    (net (code "291") (name "APM_VCC") (class "Default")
      (node (ref "J3") (pin "12") (pinfunction "12_12") (pintype "passive"))
      (node (ref "J3") (pin "13") (pinfunction "13_13") (pintype "passive"))
      (node (ref "J3") (pin "19") (pinfunction "19_19") (pintype "passive"))
      (node (ref "J3") (pin "20") (pinfunction "20_20") (pintype "passive"))
      (node (ref "J3") (pin "4") (pinfunction "4_4") (pintype "passive"))
      (node (ref "J3") (pin "5") (pinfunction "5_5") (pintype "passive"))
    )
    (net (code "292") (name "CAR_VCC") (class "Default")
      (node (ref "J3") (pin "1") (pinfunction "1_1") (pintype "passive"))
      (node (ref "J3") (pin "10") (pinfunction "10_10") (pintype "passive"))
      (node (ref "J3") (pin "16") (pinfunction "16_16") (pintype "passive"))
      (node (ref "J3") (pin "17") (pinfunction "17_17") (pintype "passive"))
      (node (ref "J3") (pin "2") (pinfunction "2_2") (pintype "passive"))
      (node (ref "J3") (pin "9") (pinfunction "9_9") (pintype "passive"))
    )
    (net (code "293") (name "ETH_GND") (class "Default")
      (node (ref "C158") (pin "2") (pinfunction "2_2") (pintype "passive"))
      (node (ref "C159") (pin "2") (pinfunction "2_2") (pintype "passive"))
      (node (ref "C160") (pin "2") (pinfunction "2_2") (pintype "passive"))
      (node (ref "C161") (pin "2") (pinfunction "2_2") (pintype "passive"))
      (node (ref "C162") (pin "2") (pinfunction "2_2") (pintype "passive"))
      (node (ref "C163") (pin "2") (pinfunction "2_2") (pintype "passive"))
      (node (ref "C165") (pin "2") (pinfunction "2_2") (pintype "passive"))
      (node (ref "C166") (pin "2") (pinfunction "2_2") (pintype "passive"))
      (node (ref "C5") (pin "2") (pinfunction "2_2") (pintype "passive"))
      (node (ref "J10") (pin "1") (pinfunction "MNT_1_1") (pintype "passive"))
      (node (ref "J10") (pin "2") (pinfunction "MNT_2_2") (pintype "passive"))
    )
    (net (code "294") (name "GND") (class "Default")
      (node (ref "C156") (pin "2") (pinfunction "2_2") (pintype "passive"))
      (node (ref "C158") (pin "1") (pinfunction "1_1") (pintype "passive"))
      (node (ref "C159") (pin "1") (pinfunction "1_1") (pintype "passive"))
      (node (ref "C160") (pin "1") (pinfunction "1_1") (pintype "passive"))
      (node (ref "C161") (pin "1") (pinfunction "1_1") (pintype "passive"))
      (node (ref "C162") (pin "1") (pinfunction "1_1") (pintype "passive"))
      (node (ref "C163") (pin "1") (pinfunction "1_1") (pintype "passive"))
      (node (ref "C164") (pin "2") (pinfunction "2_2") (pintype "passive"))
      (node (ref "C165") (pin "1") (pinfunction "1_1") (pintype "passive"))
      (node (ref "C166") (pin "1") (pinfunction "1_1") (pintype "passive"))
      (node (ref "D15") (pin "3") (pinfunction "GND_3") (pintype "power_in"))
      (node (ref "D15") (pin "8") (pinfunction "GND_8") (pintype "power_in"))
      (node (ref "D16") (pin "3") (pinfunction "GND_3") (pintype "power_in"))
      (node (ref "D16") (pin "8") (pinfunction "GND_8") (pintype "power_in"))
      (node (ref "D17") (pin "3") (pinfunction "GND_3") (pintype "power_in"))
      (node (ref "D17") (pin "8") (pinfunction "GND_8") (pintype "power_in"))
      (node (ref "D18") (pin "3") (pinfunction "GND_3") (pintype "power_in"))
      (node (ref "D18") (pin "8") (pinfunction "GND_8") (pintype "power_in"))
      (node (ref "D19") (pin "3") (pinfunction "GND_3") (pintype "power_in"))
      (node (ref "D19") (pin "8") (pinfunction "GND_8") (pintype "power_in"))
      (node (ref "D20") (pin "3") (pinfunction "GND_3") (pintype "power_in"))
      (node (ref "D20") (pin "8") (pinfunction "GND_8") (pintype "power_in"))
      (node (ref "D21") (pin "3") (pinfunction "GND_3") (pintype "power_in"))
      (node (ref "D21") (pin "8") (pinfunction "GND_8") (pintype "power_in"))
      (node (ref "D23") (pin "3") (pinfunction "GND_3") (pintype "power_in"))
      (node (ref "D23") (pin "8") (pinfunction "GND_8") (pintype "power_in"))
      (node (ref "D24") (pin "3") (pinfunction "GND_3") (pintype "power_in"))
      (node (ref "D24") (pin "8") (pinfunction "GND_8") (pintype "power_in"))
      (node (ref "D25") (pin "3") (pinfunction "GND_3") (pintype "power_in"))
      (node (ref "D25") (pin "8") (pinfunction "GND_8") (pintype "power_in"))
      (node (ref "D26") (pin "3") (pinfunction "GND_3") (pintype "power_in"))
      (node (ref "D26") (pin "8") (pinfunction "GND_8") (pintype "power_in"))
      (node (ref "D27") (pin "3") (pinfunction "GND_3") (pintype "power_in"))
      (node (ref "D27") (pin "8") (pinfunction "GND_8") (pintype "power_in"))
      (node (ref "D28") (pin "3") (pinfunction "GND_3") (pintype "power_in"))
      (node (ref "D28") (pin "8") (pinfunction "GND_8") (pintype "power_in"))
      (node (ref "D29") (pin "3") (pinfunction "GND_3") (pintype "power_in"))
      (node (ref "D29") (pin "8") (pinfunction "GND_8") (pintype "power_in"))
      (node (ref "J1") (pin "MH1") (pinfunction "MH1_MH1") (pintype "passive"))
      (node (ref "J1") (pin "MH2") (pinfunction "MH2_MH2") (pintype "passive"))
      (node (ref "J1") (pin "MH3") (pinfunction "MH3_MH3") (pintype "passive"))
      (node (ref "J1") (pin "MH4") (pinfunction "MH4_MH4") (pintype "passive"))
      (node (ref "J1") (pin "MH5") (pinfunction "MH5_MH5") (pintype "passive"))
      (node (ref "J11") (pin "1") (pinfunction "1_1") (pintype "passive"))
      (node (ref "J12") (pin "4") (pinfunction "GND_4") (pintype "passive"))
      (node (ref "J12") (pin "Shell") (pinfunction "Shield_Shell") (pintype "passive"))
      (node (ref "J3") (pin "11") (pinfunction "11_11") (pintype "passive"))
      (node (ref "J3") (pin "14") (pinfunction "14_14") (pintype "passive"))
      (node (ref "J3") (pin "15") (pinfunction "15_15") (pintype "passive"))
      (node (ref "J3") (pin "18") (pinfunction "18_18") (pintype "passive"))
      (node (ref "J3") (pin "21") (pinfunction "21_21") (pintype "passive"))
      (node (ref "J3") (pin "3") (pinfunction "3_3") (pintype "passive"))
      (node (ref "J3") (pin "6") (pinfunction "6_6") (pintype "passive"))
      (node (ref "J3") (pin "7") (pinfunction "7_7") (pintype "passive"))
      (node (ref "J3") (pin "8") (pinfunction "8_8") (pintype "passive"))
      (node (ref "J4") (pin "MH1") (pinfunction "MH1_MH1") (pintype "passive"))
      (node (ref "J4") (pin "MH2") (pinfunction "MH2_MH2") (pintype "passive"))
      (node (ref "J4") (pin "MH3") (pinfunction "MH3_MH3") (pintype "passive"))
      (node (ref "J4") (pin "MH4") (pinfunction "MH4_MH4") (pintype "passive"))
      (node (ref "J4") (pin "MH5") (pinfunction "MH5_MH5") (pintype "passive"))
      (node (ref "J5") (pin "11") (pinfunction "GND_11") (pintype "passive"))
      (node (ref "J5") (pin "17") (pinfunction "GND_17") (pintype "power_in"))
      (node (ref "J5") (pin "2") (pinfunction "GND_2") (pintype "power_in"))
      (node (ref "J5") (pin "20") (pinfunction "MNT_1_20") (pintype "passive"))
      (node (ref "J5") (pin "21") (pinfunction "MNT_2_21") (pintype "passive"))
      (node (ref "J5") (pin "22") (pinfunction "MNT_3_22") (pintype "passive"))
      (node (ref "J5") (pin "5") (pinfunction "GND_5") (pintype "passive"))
      (node (ref "J5") (pin "8") (pinfunction "GND_8") (pintype "passive"))
      (node (ref "J6") (pin "10") (pinfunction "SHLD5_10") (pintype "passive"))
      (node (ref "J6") (pin "11") (pinfunction "SHLD6_11") (pintype "passive"))
      (node (ref "J6") (pin "5") (pinfunction "GND_5") (pintype "passive"))
      (node (ref "J6") (pin "6") (pinfunction "SHLD1_6") (pintype "passive"))
      (node (ref "J6") (pin "7") (pinfunction "SHLD2_7") (pintype "passive"))
      (node (ref "J6") (pin "8") (pinfunction "SHLD3_8") (pintype "passive"))
      (node (ref "J6") (pin "9") (pinfunction "SHLD4_9") (pintype "passive"))
      (node (ref "J7") (pin "2") (pinfunction "2_2") (pintype "passive"))
      (node (ref "J8") (pin "10") (pinfunction "MNT_6_10") (pintype "passive"))
      (node (ref "J8") (pin "11") (pinfunction "MNT_7_11") (pintype "passive"))
      (node (ref "J8") (pin "13") (pinfunction "13_13") (pintype "passive"))
      (node (ref "J8") (pin "5") (pinfunction "MNT_1_5") (pintype "passive"))
      (node (ref "J8") (pin "6") (pinfunction "MNT_2_6") (pintype "passive"))
      (node (ref "J8") (pin "7") (pinfunction "MNT_3_7") (pintype "passive"))
      (node (ref "J8") (pin "8") (pinfunction "MNT_4_8") (pintype "passive"))
      (node (ref "J8") (pin "9") (pinfunction "MNT_5_9") (pintype "passive"))
      (node (ref "J9") (pin "1") (pinfunction "1_1") (pintype "passive"))
      (node (ref "MH1") (pin "1") (pinfunction "MH_1") (pintype "passive"))
      (node (ref "MH1") (pin "2") (pinfunction "V1_2") (pintype "passive"))
      (node (ref "MH1") (pin "3") (pinfunction "V2_3") (pintype "passive"))
      (node (ref "MH1") (pin "4") (pinfunction "V3_4") (pintype "passive"))
      (node (ref "MH1") (pin "5") (pinfunction "V4_5") (pintype "passive"))
      (node (ref "MH1") (pin "6") (pinfunction "V5_6") (pintype "passive"))
      (node (ref "MH1") (pin "7") (pinfunction "V6_7") (pintype "passive"))
      (node (ref "MH10") (pin "1") (pinfunction "MH_1") (pintype "passive"))
      (node (ref "MH10") (pin "2") (pinfunction "V1_2") (pintype "passive"))
      (node (ref "MH10") (pin "3") (pinfunction "V2_3") (pintype "passive"))
      (node (ref "MH10") (pin "4") (pinfunction "V3_4") (pintype "passive"))
      (node (ref "MH10") (pin "5") (pinfunction "V4_5") (pintype "passive"))
      (node (ref "MH10") (pin "6") (pinfunction "V5_6") (pintype "passive"))
      (node (ref "MH10") (pin "7") (pinfunction "V6_7") (pintype "passive"))
      (node (ref "MH11") (pin "1") (pinfunction "MH_1") (pintype "passive"))
      (node (ref "MH11") (pin "2") (pinfunction "V1_2") (pintype "passive"))
      (node (ref "MH11") (pin "3") (pinfunction "V2_3") (pintype "passive"))
      (node (ref "MH11") (pin "4") (pinfunction "V3_4") (pintype "passive"))
      (node (ref "MH11") (pin "5") (pinfunction "V4_5") (pintype "passive"))
      (node (ref "MH11") (pin "6") (pinfunction "V5_6") (pintype "passive"))
      (node (ref "MH11") (pin "7") (pinfunction "V6_7") (pintype "passive"))
      (node (ref "MH12") (pin "1") (pinfunction "MH_1") (pintype "passive"))
      (node (ref "MH12") (pin "2") (pinfunction "V1_2") (pintype "passive"))
      (node (ref "MH12") (pin "3") (pinfunction "V2_3") (pintype "passive"))
      (node (ref "MH12") (pin "4") (pinfunction "V3_4") (pintype "passive"))
      (node (ref "MH12") (pin "5") (pinfunction "V4_5") (pintype "passive"))
      (node (ref "MH12") (pin "6") (pinfunction "V5_6") (pintype "passive"))
      (node (ref "MH12") (pin "7") (pinfunction "V6_7") (pintype "passive"))
      (node (ref "MH2") (pin "1") (pinfunction "MH_1") (pintype "passive"))
      (node (ref "MH2") (pin "2") (pinfunction "V1_2") (pintype "passive"))
      (node (ref "MH2") (pin "3") (pinfunction "V2_3") (pintype "passive"))
      (node (ref "MH2") (pin "4") (pinfunction "V3_4") (pintype "passive"))
      (node (ref "MH2") (pin "5") (pinfunction "V4_5") (pintype "passive"))
      (node (ref "MH2") (pin "6") (pinfunction "V5_6") (pintype "passive"))
      (node (ref "MH2") (pin "7") (pinfunction "V6_7") (pintype "passive"))
      (node (ref "MH3") (pin "1") (pinfunction "MH_1") (pintype "passive"))
      (node (ref "MH3") (pin "2") (pinfunction "V1_2") (pintype "passive"))
      (node (ref "MH3") (pin "3") (pinfunction "V2_3") (pintype "passive"))
      (node (ref "MH3") (pin "4") (pinfunction "V3_4") (pintype "passive"))
      (node (ref "MH3") (pin "5") (pinfunction "V4_5") (pintype "passive"))
      (node (ref "MH3") (pin "6") (pinfunction "V5_6") (pintype "passive"))
      (node (ref "MH3") (pin "7") (pinfunction "V6_7") (pintype "passive"))
      (node (ref "MH4") (pin "1") (pinfunction "MH_1") (pintype "passive"))
      (node (ref "MH4") (pin "2") (pinfunction "V1_2") (pintype "passive"))
      (node (ref "MH4") (pin "3") (pinfunction "V2_3") (pintype "passive"))
      (node (ref "MH4") (pin "4") (pinfunction "V3_4") (pintype "passive"))
      (node (ref "MH4") (pin "5") (pinfunction "V4_5") (pintype "passive"))
      (node (ref "MH4") (pin "6") (pinfunction "V5_6") (pintype "passive"))
      (node (ref "MH4") (pin "7") (pinfunction "V6_7") (pintype "passive"))
      (node (ref "MH5") (pin "1") (pinfunction "MH_1") (pintype "passive"))
      (node (ref "MH5") (pin "2") (pinfunction "V1_2") (pintype "passive"))
      (node (ref "MH5") (pin "3") (pinfunction "V2_3") (pintype "passive"))
      (node (ref "MH5") (pin "4") (pinfunction "V3_4") (pintype "passive"))
      (node (ref "MH5") (pin "5") (pinfunction "V4_5") (pintype "passive"))
      (node (ref "MH5") (pin "6") (pinfunction "V5_6") (pintype "passive"))
      (node (ref "MH5") (pin "7") (pinfunction "V6_7") (pintype "passive"))
      (node (ref "MH6") (pin "1") (pinfunction "MH_1") (pintype "passive"))
      (node (ref "MH6") (pin "2") (pinfunction "V1_2") (pintype "passive"))
      (node (ref "MH6") (pin "3") (pinfunction "V2_3") (pintype "passive"))
      (node (ref "MH6") (pin "4") (pinfunction "V3_4") (pintype "passive"))
      (node (ref "MH6") (pin "5") (pinfunction "V4_5") (pintype "passive"))
      (node (ref "MH6") (pin "6") (pinfunction "V5_6") (pintype "passive"))
      (node (ref "MH6") (pin "7") (pinfunction "V6_7") (pintype "passive"))
      (node (ref "MH7") (pin "1") (pinfunction "MH_1") (pintype "passive"))
      (node (ref "MH7") (pin "2") (pinfunction "V1_2") (pintype "passive"))
      (node (ref "MH7") (pin "3") (pinfunction "V2_3") (pintype "passive"))
      (node (ref "MH7") (pin "4") (pinfunction "V3_4") (pintype "passive"))
      (node (ref "MH7") (pin "5") (pinfunction "V4_5") (pintype "passive"))
      (node (ref "MH7") (pin "6") (pinfunction "V5_6") (pintype "passive"))
      (node (ref "MH7") (pin "7") (pinfunction "V6_7") (pintype "passive"))
      (node (ref "MH8") (pin "1") (pinfunction "MH_1") (pintype "passive"))
      (node (ref "MH8") (pin "2") (pinfunction "V1_2") (pintype "passive"))
      (node (ref "MH8") (pin "3") (pinfunction "V2_3") (pintype "passive"))
      (node (ref "MH8") (pin "4") (pinfunction "V3_4") (pintype "passive"))
      (node (ref "MH8") (pin "5") (pinfunction "V4_5") (pintype "passive"))
      (node (ref "MH8") (pin "6") (pinfunction "V5_6") (pintype "passive"))
      (node (ref "MH8") (pin "7") (pinfunction "V6_7") (pintype "passive"))
      (node (ref "MH9") (pin "1") (pinfunction "MH_1") (pintype "passive"))
      (node (ref "MH9") (pin "2") (pinfunction "V1_2") (pintype "passive"))
      (node (ref "MH9") (pin "3") (pinfunction "V2_3") (pintype "passive"))
      (node (ref "MH9") (pin "4") (pinfunction "V3_4") (pintype "passive"))
      (node (ref "MH9") (pin "5") (pinfunction "V4_5") (pintype "passive"))
      (node (ref "MH9") (pin "6") (pinfunction "V5_6") (pintype "passive"))
      (node (ref "MH9") (pin "7") (pinfunction "V6_7") (pintype "passive"))
      (node (ref "Q24") (pin "1") (pinfunction "Source1_1") (pintype "passive"))
      (node (ref "Q24") (pin "4") (pinfunction "Source2_4") (pintype "passive"))
      (node (ref "Q25") (pin "1") (pinfunction "Source1_1") (pintype "passive"))
      (node (ref "Q25") (pin "4") (pinfunction "Source2_4") (pintype "passive"))
      (node (ref "Q26") (pin "2") (pinfunction "S_2") (pintype "passive"))
      (node (ref "Q27") (pin "4") (pinfunction "Source2_4") (pintype "passive"))
      (node (ref "Q28") (pin "4") (pinfunction "Source2_4") (pintype "passive"))
      (node (ref "R138") (pin "1") (pinfunction "1_1") (pintype "passive"))
      (node (ref "R139") (pin "1") (pinfunction "1_1") (pintype "passive"))
      (node (ref "R140") (pin "1") (pinfunction "1_1") (pintype "passive"))
      (node (ref "R141") (pin "1") (pinfunction "1_1") (pintype "passive"))
      (node (ref "R144") (pin "1") (pinfunction "1_1") (pintype "passive"))
      (node (ref "R146") (pin "1") (pinfunction "1_1") (pintype "passive"))
      (node (ref "R150") (pin "1") (pinfunction "1_1") (pintype "passive"))
      (node (ref "R167") (pin "1") (pinfunction "1_1") (pintype "passive"))
      (node (ref "R180") (pin "1") (pinfunction "1_1") (pintype "passive"))
      (node (ref "R181") (pin "1") (pinfunction "1_1") (pintype "passive"))
      (node (ref "U15") (pin "2") (pinfunction "GND_2") (pintype "power_in"))
      (node (ref "U16") (pin "2") (pinfunction "GND_2") (pintype "power_in"))
      (node (ref "U17") (pin "2") (pinfunction "GND_2") (pintype "power_in"))
      (node (ref "U18") (pin "1") (pinfunction "~{OE}_1") (pintype "input"))
      (node (ref "U18") (pin "3") (pinfunction "GND_3") (pintype "power_in"))
      (node (ref "U19") (pin "2") (pinfunction "GND_2") (pintype "power_in"))
      (node (ref "U20") (pin "1") (pinfunction "~{OE}_1") (pintype "input"))
      (node (ref "U20") (pin "3") (pinfunction "GND_3") (pintype "power_in"))
    )
    (net (code "297") (name "JSN_1V8_REF") (class "Default")
      (node (ref "C164") (pin "1") (pinfunction "1_1") (pintype "passive"))
      (node (ref "Q27") (pin "2") (pinfunction "Gate1_2") (pintype "passive"))
      (node (ref "Q28") (pin "2") (pinfunction "Gate1_2") (pintype "passive"))
      (node (ref "R143") (pin "2") (pinfunction "2_2") (pintype "passive"))
      (node (ref "R165") (pin "2") (pinfunction "2_2") (pintype "passive"))
      (node (ref "R170") (pin "2") (pinfunction "2_2") (pintype "passive"))
      (node (ref "R171") (pin "2") (pinfunction "2_2") (pintype "passive"))
      (node (ref "R182") (pin "1") (pinfunction "1_1") (pintype "passive"))
      (node (ref "U20") (pin "5") (pinfunction "VCC_5") (pintype "power_in"))
    )
    (net (code "298") (name "Net-(D14-A)") (class "Default")
      (node (ref "D14") (pin "2") (pinfunction "A_2") (pintype "passive"))
      (node (ref "R142") (pin "1") (pinfunction "1_1") (pintype "passive"))
    )
    (net (code "299") (name "Net-(F21-Pad2)") (class "Default")
      (node (ref "F21") (pin "2") (pinfunction "2_2") (pintype "passive"))
      (node (ref "J9") (pin "2") (pinfunction "2_2") (pintype "passive"))
    )
    (net (code "300") (name "Net-(F22-Pad2)") (class "Default")
      (node (ref "F22") (pin "2") (pinfunction "2_2") (pintype "passive"))
      (node (ref "J11") (pin "2") (pinfunction "2_2") (pintype "passive"))
    )
    (net (code "301") (name "Net-(J7-Pad1)") (class "Default")
      (node (ref "J7") (pin "1") (pinfunction "1_1") (pintype "passive"))
      (node (ref "R164") (pin "2") (pinfunction "2_2") (pintype "passive"))
    )
    (net (code "302") (name "Net-(J10-1_ANODE_GREEN{slash}1_CATHODE_YELLOW)") (class "Default")
      (node (ref "J10") (pin "P11") (pinfunction "1_ANODE_GREEN/1_CATHODE_YELLOW_P11") (pintype "passive"))
      (node (ref "R174") (pin "1") (pinfunction "1_1") (pintype "passive"))
    )
    (net (code "303") (name "Net-(J10-2_CATHODE_GREEN{slash}2_ANODE_YELLOW)") (class "Default")
      (node (ref "J10") (pin "P14") (pinfunction "2_CATHODE_GREEN/2_ANODE_YELLOW_P14") (pintype "passive"))
      (node (ref "R177") (pin "1") (pinfunction "1_1") (pintype "passive"))
    )
    (net (code "304") (name "Net-(Q25A-Gate1)") (class "Default")
      (node (ref "Q25") (pin "2") (pinfunction "Gate1_2") (pintype "passive"))
      (node (ref "R149") (pin "1") (pinfunction "1_1") (pintype "passive"))
      (node (ref "R150") (pin "2") (pinfunction "2_2") (pintype "passive"))
    )
    (net (code "305") (name "Net-(Q26-D)") (class "Default")
      (node (ref "Q26") (pin "3") (pinfunction "D_3") (pintype "passive"))
      (node (ref "R165") (pin "1") (pinfunction "1_1") (pintype "passive"))
      (node (ref "R166") (pin "1") (pinfunction "1_1") (pintype "passive"))
    )
    (net (code "306") (name "Net-(Q27A-Source1)") (class "Default")
      (node (ref "Q27") (pin "1") (pinfunction "Source1_1") (pintype "passive"))
      (node (ref "R170") (pin "1") (pinfunction "1_1") (pintype "passive"))
      (node (ref "R172") (pin "1") (pinfunction "1_1") (pintype "passive"))
    )
    (net (code "307") (name "Net-(Q27B-Gate2)") (class "Default")
      (node (ref "Q27") (pin "5") (pinfunction "Gate2_5") (pintype "passive"))
      (node (ref "R178") (pin "1") (pinfunction "1_1") (pintype "passive"))
      (node (ref "R180") (pin "2") (pinfunction "2_2") (pintype "passive"))
    )
    (net (code "308") (name "Net-(Q28A-Source1)") (class "Default")
      (node (ref "Q28") (pin "1") (pinfunction "Source1_1") (pintype "passive"))
      (node (ref "R171") (pin "1") (pinfunction "1_1") (pintype "passive"))
      (node (ref "R173") (pin "1") (pinfunction "1_1") (pintype "passive"))
    )
    (net (code "309") (name "Net-(Q28B-Gate2)") (class "Default")
      (node (ref "Q28") (pin "5") (pinfunction "Gate2_5") (pintype "passive"))
      (node (ref "R179") (pin "1") (pinfunction "1_1") (pintype "passive"))
      (node (ref "R181") (pin "2") (pinfunction "2_2") (pintype "passive"))
    )
    (net (code "310") (name "Net-(U15-EN)") (class "Default")
      (node (ref "R139") (pin "2") (pinfunction "2_2") (pintype "passive"))
      (node (ref "U15") (pin "4") (pinfunction "EN_4") (pintype "input"))
    )
    (net (code "311") (name "Net-(U16-EN)") (class "Default")
      (node (ref "R141") (pin "2") (pinfunction "2_2") (pintype "passive"))
      (node (ref "U16") (pin "4") (pinfunction "EN_4") (pintype "input"))
    )
    (net (code "312") (name "Net-(U18A-Y)") (class "Default")
      (node (ref "R147") (pin "1") (pinfunction "1_1") (pintype "passive"))
      (node (ref "U18") (pin "4") (pinfunction "Y_4") (pintype "tri_state"))
    )
    (net (code "313") (name "Net-(U20A-A)") (class "Default")
      (node (ref "R182") (pin "2") (pinfunction "2_2") (pintype "passive"))
      (node (ref "R183") (pin "1") (pinfunction "1_1") (pintype "passive"))
      (node (ref "R184") (pin "1") (pinfunction "1_1") (pintype "passive"))
      (node (ref "U20") (pin "2") (pinfunction "A_2") (pintype "input"))
    )
    (net (code "314") (name "PRE_VCC") (class "Default")
      (node (ref "R148") (pin "2") (pinfunction "2_2") (pintype "passive"))
    )
    (net (code "315") (name "unconnected-(D15-IO1-Pad1)") (class "Default")
      (node (ref "D15") (pin "1") (pinfunction "IO1_1") (pintype "bidirectional"))
    )
    (net (code "316") (name "unconnected-(D15-IO2-Pad2)") (class "Default")
      (node (ref "D15") (pin "2") (pinfunction "IO2_2") (pintype "bidirectional"))
    )
    (net (code "317") (name "unconnected-(D15-IO3-Pad4)") (class "Default")
      (node (ref "D15") (pin "4") (pinfunction "IO3_4") (pintype "bidirectional"))
    )
    (net (code "318") (name "unconnected-(D15-IO4-Pad5)") (class "Default")
      (node (ref "D15") (pin "5") (pinfunction "IO4_5") (pintype "bidirectional"))
    )
    (net (code "319") (name "unconnected-(D15-NC-Pad6)") (class "Default")
      (node (ref "D15") (pin "6") (pinfunction "NC_6") (pintype "passive"))
    )
    (net (code "320") (name "unconnected-(D15-NC-Pad7)") (class "Default")
      (node (ref "D15") (pin "7") (pinfunction "NC_7") (pintype "passive"))
    )
    (net (code "321") (name "unconnected-(D15-NC-Pad9)") (class "Default")
      (node (ref "D15") (pin "9") (pinfunction "NC_9") (pintype "passive"))
    )
    (net (code "322") (name "unconnected-(D15-NC-Pad10)") (class "Default")
      (node (ref "D15") (pin "10") (pinfunction "NC_10") (pintype "passive"))
    )
    (net (code "323") (name "unconnected-(D16-IO1-Pad1)") (class "Default")
      (node (ref "D16") (pin "1") (pinfunction "IO1_1") (pintype "bidirectional"))
    )
    (net (code "324") (name "unconnected-(D16-IO2-Pad2)") (class "Default")
      (node (ref "D16") (pin "2") (pinfunction "IO2_2") (pintype "bidirectional"))
    )
    (net (code "325") (name "unconnected-(D16-IO3-Pad4)") (class "Default")
      (node (ref "D16") (pin "4") (pinfunction "IO3_4") (pintype "bidirectional"))
    )
    (net (code "326") (name "unconnected-(D16-IO4-Pad5)") (class "Default")
      (node (ref "D16") (pin "5") (pinfunction "IO4_5") (pintype "bidirectional"))
    )
    (net (code "327") (name "unconnected-(D16-NC-Pad6)") (class "Default")
      (node (ref "D16") (pin "6") (pinfunction "NC_6") (pintype "passive"))
    )
    (net (code "328") (name "unconnected-(D16-NC-Pad7)") (class "Default")
      (node (ref "D16") (pin "7") (pinfunction "NC_7") (pintype "passive"))
    )
    (net (code "329") (name "unconnected-(D16-NC-Pad9)") (class "Default")
      (node (ref "D16") (pin "9") (pinfunction "NC_9") (pintype "passive"))
    )
    (net (code "330") (name "unconnected-(D16-NC-Pad10)") (class "Default")
      (node (ref "D16") (pin "10") (pinfunction "NC_10") (pintype "passive"))
    )
    (net (code "331") (name "unconnected-(D17-IO1-Pad1)") (class "Default")
      (node (ref "D17") (pin "1") (pinfunction "IO1_1") (pintype "bidirectional"))
    )
    (net (code "332") (name "unconnected-(D17-IO2-Pad2)") (class "Default")
      (node (ref "D17") (pin "2") (pinfunction "IO2_2") (pintype "bidirectional"))
    )
    (net (code "333") (name "unconnected-(D17-IO3-Pad4)") (class "Default")
      (node (ref "D17") (pin "4") (pinfunction "IO3_4") (pintype "bidirectional"))
    )
    (net (code "334") (name "unconnected-(D17-IO4-Pad5)") (class "Default")
      (node (ref "D17") (pin "5") (pinfunction "IO4_5") (pintype "bidirectional"))
    )
    (net (code "335") (name "unconnected-(D17-NC-Pad6)") (class "Default")
      (node (ref "D17") (pin "6") (pinfunction "NC_6") (pintype "passive"))
    )
    (net (code "336") (name "unconnected-(D17-NC-Pad7)") (class "Default")
      (node (ref "D17") (pin "7") (pinfunction "NC_7") (pintype "passive"))
    )
    (net (code "337") (name "unconnected-(D17-NC-Pad9)") (class "Default")
      (node (ref "D17") (pin "9") (pinfunction "NC_9") (pintype "passive"))
    )
    (net (code "338") (name "unconnected-(D17-NC-Pad10)") (class "Default")
      (node (ref "D17") (pin "10") (pinfunction "NC_10") (pintype "passive"))
    )
    (net (code "339") (name "unconnected-(D18-IO1-Pad1)") (class "Default")
      (node (ref "D18") (pin "1") (pinfunction "IO1_1") (pintype "bidirectional"))
    )
    (net (code "340") (name "unconnected-(D18-IO2-Pad2)") (class "Default")
      (node (ref "D18") (pin "2") (pinfunction "IO2_2") (pintype "bidirectional"))
    )
    (net (code "341") (name "unconnected-(D18-IO3-Pad4)") (class "Default")
      (node (ref "D18") (pin "4") (pinfunction "IO3_4") (pintype "bidirectional"))
    )
    (net (code "342") (name "unconnected-(D18-IO4-Pad5)") (class "Default")
      (node (ref "D18") (pin "5") (pinfunction "IO4_5") (pintype "bidirectional"))
    )
    (net (code "343") (name "unconnected-(D18-NC-Pad6)") (class "Default")
      (node (ref "D18") (pin "6") (pinfunction "NC_6") (pintype "passive"))
    )
    (net (code "344") (name "unconnected-(D18-NC-Pad7)") (class "Default")
      (node (ref "D18") (pin "7") (pinfunction "NC_7") (pintype "passive"))
    )
    (net (code "345") (name "unconnected-(D18-NC-Pad9)") (class "Default")
      (node (ref "D18") (pin "9") (pinfunction "NC_9") (pintype "passive"))
    )
    (net (code "346") (name "unconnected-(D18-NC-Pad10)") (class "Default")
      (node (ref "D18") (pin "10") (pinfunction "NC_10") (pintype "passive"))
    )
    (net (code "347") (name "unconnected-(D23-IO4-Pad5)") (class "Default")
      (node (ref "D23") (pin "5") (pinfunction "IO4_5") (pintype "bidirectional"))
    )
    (net (code "348") (name "unconnected-(D23-NC-Pad6)") (class "Default")
      (node (ref "D23") (pin "6") (pinfunction "NC_6") (pintype "passive"))
    )
    (net (code "349") (name "unconnected-(D23-NC-Pad7)") (class "Default")
      (node (ref "D23") (pin "7") (pinfunction "NC_7") (pintype "passive"))
    )
    (net (code "350") (name "unconnected-(D23-NC-Pad9)") (class "Default")
      (node (ref "D23") (pin "9") (pinfunction "NC_9") (pintype "passive"))
    )
    (net (code "351") (name "unconnected-(D23-NC-Pad10)") (class "Default")
      (node (ref "D23") (pin "10") (pinfunction "NC_10") (pintype "passive"))
    )
    (net (code "352") (name "unconnected-(D24-IO1-Pad1)") (class "Default")
      (node (ref "D24") (pin "1") (pinfunction "IO1_1") (pintype "bidirectional"))
    )
    (net (code "353") (name "unconnected-(D24-IO2-Pad2)") (class "Default")
      (node (ref "D24") (pin "2") (pinfunction "IO2_2") (pintype "bidirectional"))
    )
    (net (code "354") (name "unconnected-(D24-IO3-Pad4)") (class "Default")
      (node (ref "D24") (pin "4") (pinfunction "IO3_4") (pintype "bidirectional"))
    )
    (net (code "355") (name "unconnected-(D24-IO4-Pad5)") (class "Default")
      (node (ref "D24") (pin "5") (pinfunction "IO4_5") (pintype "bidirectional"))
    )
    (net (code "356") (name "unconnected-(D24-NC-Pad6)") (class "Default")
      (node (ref "D24") (pin "6") (pinfunction "NC_6") (pintype "passive"))
    )
    (net (code "357") (name "unconnected-(D24-NC-Pad7)") (class "Default")
      (node (ref "D24") (pin "7") (pinfunction "NC_7") (pintype "passive"))
    )
    (net (code "358") (name "unconnected-(D24-NC-Pad9)") (class "Default")
      (node (ref "D24") (pin "9") (pinfunction "NC_9") (pintype "passive"))
    )
    (net (code "359") (name "unconnected-(D24-NC-Pad10)") (class "Default")
      (node (ref "D24") (pin "10") (pinfunction "NC_10") (pintype "passive"))
    )
    (net (code "360") (name "unconnected-(D25-IO1-Pad1)") (class "Default")
      (node (ref "D25") (pin "1") (pinfunction "IO1_1") (pintype "bidirectional"))
    )
    (net (code "361") (name "unconnected-(D25-IO2-Pad2)") (class "Default")
      (node (ref "D25") (pin "2") (pinfunction "IO2_2") (pintype "bidirectional"))
    )
    (net (code "362") (name "unconnected-(D25-IO3-Pad4)") (class "Default")
      (node (ref "D25") (pin "4") (pinfunction "IO3_4") (pintype "bidirectional"))
    )
    (net (code "363") (name "unconnected-(D25-IO4-Pad5)") (class "Default")
      (node (ref "D25") (pin "5") (pinfunction "IO4_5") (pintype "bidirectional"))
    )
    (net (code "364") (name "unconnected-(D25-NC-Pad6)") (class "Default")
      (node (ref "D25") (pin "6") (pinfunction "NC_6") (pintype "passive"))
    )
    (net (code "365") (name "unconnected-(D25-NC-Pad7)") (class "Default")
      (node (ref "D25") (pin "7") (pinfunction "NC_7") (pintype "passive"))
    )
    (net (code "366") (name "unconnected-(D25-NC-Pad9)") (class "Default")
      (node (ref "D25") (pin "9") (pinfunction "NC_9") (pintype "passive"))
    )
    (net (code "367") (name "unconnected-(D25-NC-Pad10)") (class "Default")
      (node (ref "D25") (pin "10") (pinfunction "NC_10") (pintype "passive"))
    )
    (net (code "368") (name "unconnected-(D26-IO1-Pad1)") (class "Default")
      (node (ref "D26") (pin "1") (pinfunction "IO1_1") (pintype "bidirectional"))
    )
    (net (code "369") (name "unconnected-(D26-IO2-Pad2)") (class "Default")
      (node (ref "D26") (pin "2") (pinfunction "IO2_2") (pintype "bidirectional"))
    )
    (net (code "370") (name "unconnected-(D26-IO3-Pad4)") (class "Default")
      (node (ref "D26") (pin "4") (pinfunction "IO3_4") (pintype "bidirectional"))
    )
    (net (code "371") (name "unconnected-(D26-IO4-Pad5)") (class "Default")
      (node (ref "D26") (pin "5") (pinfunction "IO4_5") (pintype "bidirectional"))
    )
    (net (code "372") (name "unconnected-(D26-NC-Pad6)") (class "Default")
      (node (ref "D26") (pin "6") (pinfunction "NC_6") (pintype "passive"))
    )
    (net (code "373") (name "unconnected-(D26-NC-Pad7)") (class "Default")
      (node (ref "D26") (pin "7") (pinfunction "NC_7") (pintype "passive"))
    )
    (net (code "374") (name "unconnected-(D26-NC-Pad9)") (class "Default")
      (node (ref "D26") (pin "9") (pinfunction "NC_9") (pintype "passive"))
    )
    (net (code "375") (name "unconnected-(D26-NC-Pad10)") (class "Default")
      (node (ref "D26") (pin "10") (pinfunction "NC_10") (pintype "passive"))
    )
    (net (code "376") (name "unconnected-(D27-NC-Pad6)") (class "Default")
      (node (ref "D27") (pin "6") (pinfunction "NC_6") (pintype "passive"))
    )
    (net (code "377") (name "unconnected-(D27-NC-Pad7)") (class "Default")
      (node (ref "D27") (pin "7") (pinfunction "NC_7") (pintype "passive"))
    )
    (net (code "378") (name "unconnected-(D27-NC-Pad9)") (class "Default")
      (node (ref "D27") (pin "9") (pinfunction "NC_9") (pintype "passive"))
    )
    (net (code "379") (name "unconnected-(D27-NC-Pad10)") (class "Default")
      (node (ref "D27") (pin "10") (pinfunction "NC_10") (pintype "passive"))
    )
    (net (code "380") (name "unconnected-(D28-NC-Pad6)") (class "Default")
      (node (ref "D28") (pin "6") (pinfunction "NC_6") (pintype "passive"))
    )
    (net (code "381") (name "unconnected-(D28-NC-Pad7)") (class "Default")
      (node (ref "D28") (pin "7") (pinfunction "NC_7") (pintype "passive"))
    )
    (net (code "382") (name "unconnected-(D28-NC-Pad9)") (class "Default")
      (node (ref "D28") (pin "9") (pinfunction "NC_9") (pintype "passive"))
    )
    (net (code "383") (name "unconnected-(D28-NC-Pad10)") (class "Default")
      (node (ref "D28") (pin "10") (pinfunction "NC_10") (pintype "passive"))
    )
    (net (code "384") (name "unconnected-(D29-IO4-Pad5)") (class "Default")
      (node (ref "D29") (pin "5") (pinfunction "IO4_5") (pintype "bidirectional"))
    )
    (net (code "385") (name "unconnected-(D29-NC-Pad6)") (class "Default")
      (node (ref "D29") (pin "6") (pinfunction "NC_6") (pintype "passive"))
    )
    (net (code "386") (name "unconnected-(D29-NC-Pad7)") (class "Default")
      (node (ref "D29") (pin "7") (pinfunction "NC_7") (pintype "passive"))
    )
    (net (code "387") (name "unconnected-(D29-NC-Pad9)") (class "Default")
      (node (ref "D29") (pin "9") (pinfunction "NC_9") (pintype "passive"))
    )
    (net (code "388") (name "unconnected-(D29-NC-Pad10)") (class "Default")
      (node (ref "D29") (pin "10") (pinfunction "NC_10") (pintype "passive"))
    )
    (net (code "389") (name "unconnected-(J5-RSVD-Pad14)") (class "Default")
      (node (ref "J5") (pin "14") (pinfunction "RSVD_14") (pintype "bidirectional+no_connect"))
    )
    (net (code "390") (name "unconnected-(J6-ID-Pad4)") (class "Default")
      (node (ref "J6") (pin "4") (pinfunction "ID_4") (pintype "passive+no_connect"))
    )
    (net (code "391") (name "unconnected-(Q23A-Drain1-Pad6)") (class "Default")
      (node (ref "Q23") (pin "6") (pinfunction "Drain1_6") (pintype "passive"))
    )
    (net (code "392") (name "unconnected-(Q23A-Gate1-Pad2)") (class "Default")
      (node (ref "Q23") (pin "2") (pinfunction "Gate1_2") (pintype "passive"))
    )
    (net (code "393") (name "unconnected-(Q23A-Source1-Pad1)") (class "Default")
      (node (ref "Q23") (pin "1") (pinfunction "Source1_1") (pintype "passive"))
    )
    (net (code "394") (name "unconnected-(Q23B-Drain2-Pad3)") (class "Default")
      (node (ref "Q23") (pin "3") (pinfunction "Drain2_3") (pintype "passive"))
    )
    (net (code "395") (name "unconnected-(Q23B-Gate2-Pad5)") (class "Default")
      (node (ref "Q23") (pin "5") (pinfunction "Gate2_5") (pintype "passive"))
    )
    (net (code "396") (name "unconnected-(Q23B-Source2-Pad4)") (class "Default")
      (node (ref "Q23") (pin "4") (pinfunction "Source2_4") (pintype "passive"))
    )
    (net (code "397") (name "unconnected-(Q24A-Drain1-Pad6)") (class "Default")
      (node (ref "Q24") (pin "6") (pinfunction "Drain1_6") (pintype "passive"))
    )
    (net (code "398") (name "unconnected-(Q24B-Drain2-Pad3)") (class "Default")
      (node (ref "Q24") (pin "3") (pinfunction "Drain2_3") (pintype "passive"))
    )
    (net (code "399") (name "unconnected-(Q25B-Drain2-Pad3)") (class "Default")
      (node (ref "Q25") (pin "3") (pinfunction "Drain2_3") (pintype "passive"))
    )
    (net (code "400") (name "unconnected-(U15-nFLG-Pad3)") (class "Default")
      (node (ref "U15") (pin "3") (pinfunction "nFLG_3") (pintype "output+no_connect"))
    )
    (net (code "401") (name "unconnected-(U16-nFLG-Pad3)") (class "Default")
      (node (ref "U16") (pin "3") (pinfunction "nFLG_3") (pintype "output+no_connect"))
    )
    (net (code "402") (name "unconnected-(U17-nFLG-Pad3)") (class "Default")
      (node (ref "U17") (pin "3") (pinfunction "nFLG_3") (pintype "output+no_connect"))
    )
    (net (code "403") (name "unconnected-(U19-nFLG-Pad3)") (class "Default")
      (node (ref "U19") (pin "3") (pinfunction "nFLG_3") (pintype "output+no_connect"))
    )
  )
)
